# EA08AI-V2.net
KiCad netlist of a schematic drawn in Altium Designer
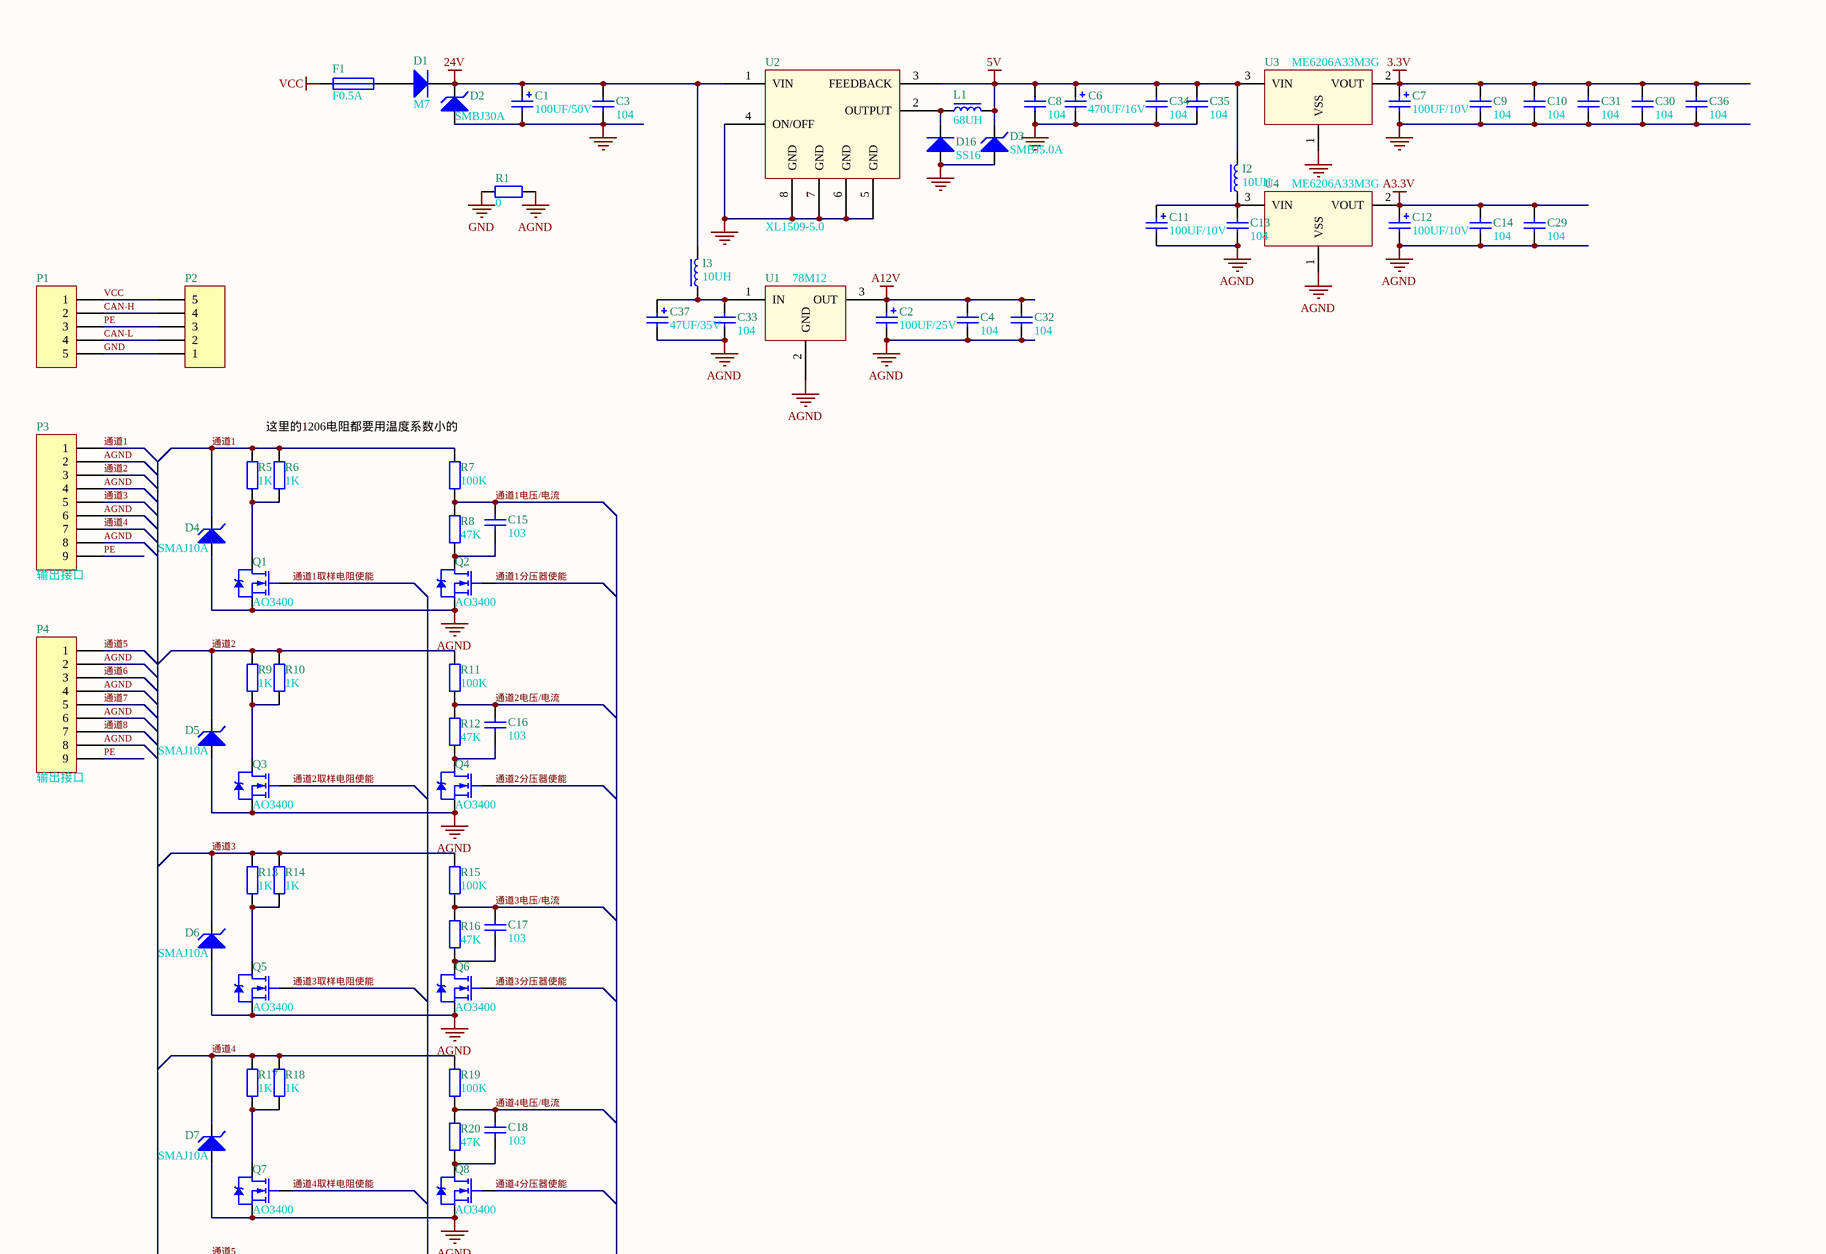
[diagram p0: EA08AI-V2.SchDoc, top]
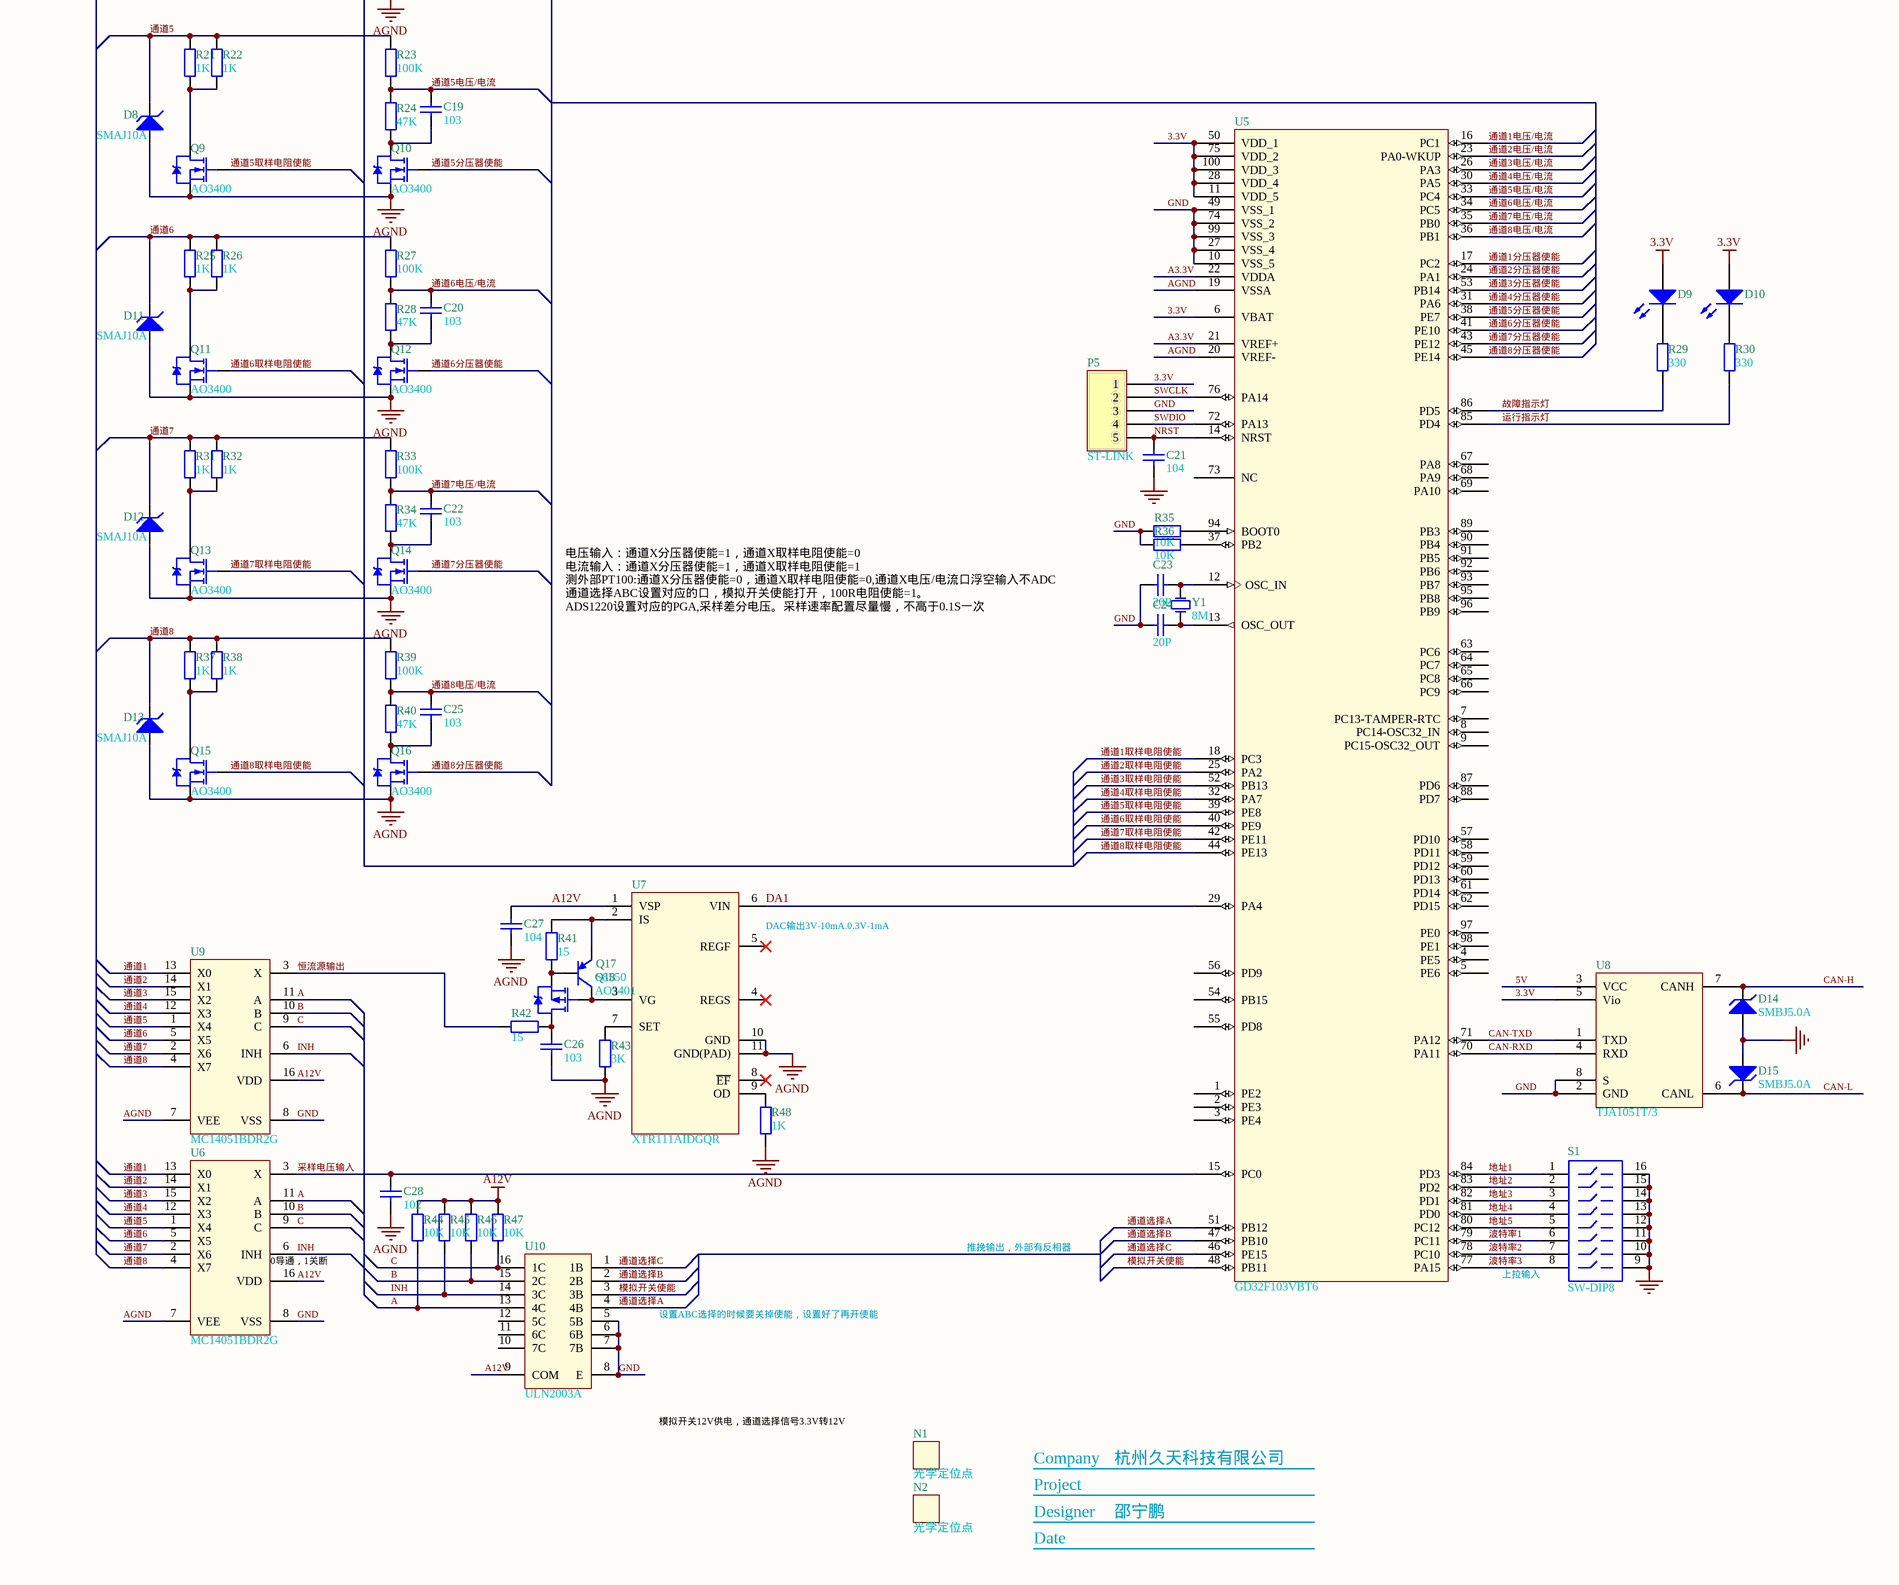
[diagram p1: EA08AI-V2.SchDoc, bottom]

(export (version "E")
  (design (tool "Eeschema 10.0.6"))
  (components
    (comp (ref "C1")
      (value "100UF/50V")
      (footprint "贴片固态电容8*10-M")
      (description "Polarized Capacitor (Radial)")
      (fields (field (name "PUBLISHER") "Altium Limited"))
      (libsource (lib "元件2.0") (part "Cap Pol1"))
    )
    (comp (ref "C2")
      (value "100UF/25V")
      (footprint "贴片固态电容6.3*5.3-M")
      (description "Polarized Capacitor (Radial)")
      (fields (field (name "PUBLISHER") "Altium Limited"))
      (libsource (lib "元件2.0") (part "Cap Pol1"))
    )
    (comp (ref "C3")
      (value "104")
      (footprint "C-0603")
      (description "Capacitor")
      (fields (field (name "PUBLISHER") "Altium Limited"))
      (libsource (lib "元件2.0") (part "Cap"))
    )
    (comp (ref "C4")
      (value "104")
      (footprint "C-0603")
      (description "Capacitor")
      (fields (field (name "PUBLISHER") "Altium Limited"))
      (libsource (lib "元件2.0") (part "Cap"))
    )
    (comp (ref "C6")
      (value "470UF/16V")
      (footprint "贴片固态电容8*10-M")
      (description "Polarized Capacitor (Radial)")
      (fields (field (name "PUBLISHER") "Altium Limited"))
      (libsource (lib "元件2.0") (part "Cap Pol1"))
    )
    (comp (ref "C7")
      (value "100UF/10V")
      (footprint "贴片固态电容5*5.3")
      (description "Polarized Capacitor (Radial)")
      (fields (field (name "PUBLISHER") "Altium Limited"))
      (libsource (lib "元件2.0") (part "Cap Pol1"))
    )
    (comp (ref "C8")
      (value "104")
      (footprint "C-0603")
      (description "Capacitor")
      (fields (field (name "PUBLISHER") "Altium Limited"))
      (libsource (lib "元件2.0") (part "Cap"))
    )
    (comp (ref "C9")
      (value "104")
      (footprint "C-0603")
      (description "Capacitor")
      (fields (field (name "PUBLISHER") "Altium Limited"))
      (libsource (lib "元件2.0") (part "Cap"))
    )
    (comp (ref "C10")
      (value "104")
      (footprint "C-0603")
      (description "Capacitor")
      (fields (field (name "PUBLISHER") "Altium Limited"))
      (libsource (lib "元件2.0") (part "Cap"))
    )
    (comp (ref "C11")
      (value "100UF/10V")
      (footprint "贴片固态电容5*5.3")
      (description "Polarized Capacitor (Radial)")
      (fields (field (name "PUBLISHER") "Altium Limited"))
      (libsource (lib "元件2.0") (part "Cap Pol1"))
    )
    (comp (ref "C12")
      (value "100UF/10V")
      (footprint "贴片固态电容5*5.3")
      (description "Polarized Capacitor (Radial)")
      (fields (field (name "PUBLISHER") "Altium Limited"))
      (libsource (lib "元件2.0") (part "Cap Pol1"))
    )
    (comp (ref "C13")
      (value "104")
      (footprint "C-0603")
      (description "Capacitor")
      (fields (field (name "PUBLISHER") "Altium Limited"))
      (libsource (lib "元件2.0") (part "Cap"))
    )
    (comp (ref "C14")
      (value "104")
      (footprint "C-0603")
      (description "Capacitor")
      (fields (field (name "PUBLISHER") "Altium Limited"))
      (libsource (lib "元件2.0") (part "Cap"))
    )
    (comp (ref "C15")
      (value "103")
      (footprint "C-0603")
      (description "0805")
      (fields (field (name "PUBLISHER") "Altium Limited"))
      (libsource (lib "2电容-V1.0") (part "Cap-0603"))
    )
    (comp (ref "C16")
      (value "103")
      (footprint "C-0603")
      (description "0805")
      (fields (field (name "PUBLISHER") "Altium Limited"))
      (libsource (lib "2电容-V1.0") (part "Cap-0603"))
    )
    (comp (ref "C17")
      (value "103")
      (footprint "C-0603")
      (description "0805")
      (fields (field (name "PUBLISHER") "Altium Limited"))
      (libsource (lib "2电容-V1.0") (part "Cap-0603"))
    )
    (comp (ref "C18")
      (value "103")
      (footprint "C-0603")
      (description "0805")
      (fields (field (name "PUBLISHER") "Altium Limited"))
      (libsource (lib "2电容-V1.0") (part "Cap-0603"))
    )
    (comp (ref "C19")
      (value "103")
      (footprint "C-0603")
      (description "0805")
      (fields (field (name "PUBLISHER") "Altium Limited"))
      (libsource (lib "2电容-V1.0") (part "Cap-0603"))
    )
    (comp (ref "C20")
      (value "103")
      (footprint "C-0603")
      (description "0805")
      (fields (field (name "PUBLISHER") "Altium Limited"))
      (libsource (lib "2电容-V1.0") (part "Cap-0603"))
    )
    (comp (ref "C21")
      (value "104")
      (footprint "C-0603")
      (description "Capacitor")
      (fields (field (name "PUBLISHER") "Altium Limited"))
      (libsource (lib "元件2.0") (part "Cap"))
    )
    (comp (ref "C22")
      (value "103")
      (footprint "C-0603")
      (description "0805")
      (fields (field (name "PUBLISHER") "Altium Limited"))
      (libsource (lib "2电容-V1.0") (part "Cap-0603"))
    )
    (comp (ref "C23")
      (value "20P")
      (footprint "C-0603")
      (description "0805")
      (fields (field (name "PUBLISHER") "Altium Limited"))
      (libsource (lib "2电容-V1.0") (part "Cap-0603"))
    )
    (comp (ref "C24")
      (value "20P")
      (footprint "C-0603")
      (description "0805")
      (fields (field (name "PUBLISHER") "Altium Limited"))
      (libsource (lib "2电容-V1.0") (part "Cap-0603"))
    )
    (comp (ref "C25")
      (value "103")
      (footprint "C-0603")
      (description "0805")
      (fields (field (name "PUBLISHER") "Altium Limited"))
      (libsource (lib "2电容-V1.0") (part "Cap-0603"))
    )
    (comp (ref "C26")
      (value "103")
      (footprint "C-0603")
      (description "0805")
      (fields (field (name "PUBLISHER") "Altium Limited"))
      (libsource (lib "2电容-V1.0") (part "Cap-0603"))
    )
    (comp (ref "C27")
      (value "104")
      (footprint "C-0603")
      (description "Capacitor")
      (fields (field (name "PUBLISHER") "Altium Limited"))
      (libsource (lib "元件2.0") (part "Cap"))
    )
    (comp (ref "C28")
      (value "102")
      (footprint "C-0603")
      (description "Capacitor")
      (fields (field (name "PUBLISHER") "Altium Limited"))
      (libsource (lib "元件2.0") (part "Cap"))
    )
    (comp (ref "C29")
      (value "104")
      (footprint "C-0603")
      (description "Capacitor")
      (fields (field (name "PUBLISHER") "Altium Limited"))
      (libsource (lib "元件2.0") (part "Cap"))
    )
    (comp (ref "C30")
      (value "104")
      (footprint "C-0603")
      (description "Capacitor")
      (fields (field (name "PUBLISHER") "Altium Limited"))
      (libsource (lib "元件2.0") (part "Cap"))
    )
    (comp (ref "C31")
      (value "104")
      (footprint "C-0603")
      (description "Capacitor")
      (fields (field (name "PUBLISHER") "Altium Limited"))
      (libsource (lib "元件2.0") (part "Cap"))
    )
    (comp (ref "C32")
      (value "104")
      (footprint "C-0603")
      (description "Capacitor")
      (fields (field (name "PUBLISHER") "Altium Limited"))
      (libsource (lib "元件2.0") (part "Cap"))
    )
    (comp (ref "C33")
      (value "104")
      (footprint "C-0603")
      (description "Capacitor")
      (fields (field (name "PUBLISHER") "Altium Limited"))
      (libsource (lib "元件2.0") (part "Cap"))
    )
    (comp (ref "C34")
      (value "104")
      (footprint "C-0603")
      (description "Capacitor")
      (fields (field (name "PUBLISHER") "Altium Limited"))
      (libsource (lib "元件2.0") (part "Cap"))
    )
    (comp (ref "C35")
      (value "104")
      (footprint "C-0603")
      (description "Capacitor")
      (fields (field (name "PUBLISHER") "Altium Limited"))
      (libsource (lib "元件2.0") (part "Cap"))
    )
    (comp (ref "C36")
      (value "104")
      (footprint "C-0603")
      (description "Capacitor")
      (fields (field (name "PUBLISHER") "Altium Limited"))
      (libsource (lib "元件2.0") (part "Cap"))
    )
    (comp (ref "C37")
      (value "47UF/35V")
      (footprint "贴片固态电容6.3*5.3-M")
      (description "Polarized Capacitor (Radial)")
      (fields (field (name "PUBLISHER") "Altium Limited"))
      (libsource (lib "元件2.0") (part "Cap Pol1"))
    )
    (comp (ref "D1")
      (value "M7")
      (footprint "SMA")
      (description "SMA")
      (fields (field (name "PUBLISHER") "Altium Limited"))
      (libsource (lib "4二极管-V1.1") (part "M7"))
    )
    (comp (ref "D2")
      (value "SMBJ30A")
      (footprint "SMB")
      (description "SMB")
      (libsource (lib "4二极管-V1.1") (part "TVS-1"))
    )
    (comp (ref "D3")
      (value "SMBJ5.0A")
      (footprint "SMB")
      (description "SMB")
      (libsource (lib "4二极管-V1.1") (part "TVS-1"))
    )
    (comp (ref "D4")
      (value "SMAJ10A")
      (footprint "SMA")
      (description "SMB")
      (libsource (lib "4二极管-V1.1") (part "TVS-1"))
    )
    (comp (ref "D5")
      (value "SMAJ10A")
      (footprint "SMA")
      (description "SMB")
      (libsource (lib "4二极管-V1.1") (part "TVS-1"))
    )
    (comp (ref "D6")
      (value "SMAJ10A")
      (footprint "SMA")
      (description "SMB")
      (libsource (lib "4二极管-V1.1") (part "TVS-1"))
    )
    (comp (ref "D7")
      (value "SMAJ10A")
      (footprint "SMA")
      (description "SMB")
      (libsource (lib "4二极管-V1.1") (part "TVS-1"))
    )
    (comp (ref "D8")
      (value "SMAJ10A")
      (footprint "SMA")
      (description "SMB")
      (libsource (lib "4二极管-V1.1") (part "TVS-1"))
    )
    (comp (ref "D9")
      (value "~")
      (footprint "LED Φ3红2.54mm")
      (fields (field (name "PUBLISHER") "Altium Limited"))
      (libsource (lib "4二极管-V1.1") (part "LED-0603-Blue"))
    )
    (comp (ref "D10")
      (value "~")
      (footprint "LED Φ3绿2.54mm")
      (fields (field (name "PUBLISHER") "Altium Limited"))
      (libsource (lib "4二极管-V1.1") (part "LED-0603-Blue"))
    )
    (comp (ref "D11")
      (value "SMAJ10A")
      (footprint "SMA")
      (description "SMB")
      (libsource (lib "4二极管-V1.1") (part "TVS-1"))
    )
    (comp (ref "D12")
      (value "SMAJ10A")
      (footprint "SMA")
      (description "SMB")
      (libsource (lib "4二极管-V1.1") (part "TVS-1"))
    )
    (comp (ref "D13")
      (value "SMAJ10A")
      (footprint "SMA")
      (description "SMB")
      (libsource (lib "4二极管-V1.1") (part "TVS-1"))
    )
    (comp (ref "D14")
      (value "SMBJ5.0A")
      (footprint "SMB")
      (description "SMB")
      (libsource (lib "4二极管-V1.1") (part "TVS-1"))
    )
    (comp (ref "D15")
      (value "SMBJ5.0A")
      (footprint "SMB")
      (description "SMB")
      (libsource (lib "4二极管-V1.1") (part "TVS-1"))
    )
    (comp (ref "D16")
      (value "SS16")
      (footprint "SMA")
      (description "SMA")
      (libsource (lib "4二极管-V1.1") (part "SS14"))
    )
    (comp (ref "F1")
      (value "F0.5A")
      (footprint "FUSE-1808")
      (description "Fuse")
      (fields (field (name "PUBLISHER") "Altium Limited"))
      (libsource (lib "11其他元件-V1.0") (part "Fuse 1"))
    )
    (comp (ref "I2") (value "10UH") (footprint "CD54") (libsource (lib "3电感-V1.0") (part "Inductance3")))
    (comp (ref "I3") (value "10UH") (footprint "CD54") (libsource (lib "3电感-V1.0") (part "Inductance3")))
    (comp (ref "L1") (value "68UH") (footprint "CD75") (libsource (lib "3电感-V1.0") (part "Inductance3")))
    (comp (ref "N1") (value "光学定位点") (footprint "MARK-1mm-3mm") (libsource (lib "11其他元件-V1.0") (part "无引脚")))
    (comp (ref "N2") (value "光学定位点") (footprint "MARK-1mm-3mm") (libsource (lib "11其他元件-V1.0") (part "无引脚")))
    (comp (ref "P1")
      (value "~")
      (footprint "弯针5.08-M-5P")
      (description "Header, 5-Pin")
      (fields (field (name "PUBLISHER") "Altium Limited"))
      (libsource (lib "5排针-V1.0") (part "Header 5"))
    )
    (comp (ref "P2")
      (value "~")
      (footprint "KF2EDGVC-5.08-5P弯针")
      (description "Header, 5-Pin")
      (fields (field (name "PUBLISHER") "Altium Limited"))
      (libsource (lib "") (part "Header 5_1"))
    )
    (comp (ref "P3")
      (value "输出接口")
      (footprint "KF2EDGVC-5.08-9P")
      (description "Header, 9-Pin")
      (fields (field (name "PUBLISHER") "Altium Limited"))
      (libsource (lib "5排针-V1.0") (part "Header 9"))
    )
    (comp (ref "P4")
      (value "输出接口")
      (footprint "KF2EDGVC-5.08-9P")
      (description "Header, 9-Pin")
      (fields (field (name "PUBLISHER") "Altium Limited"))
      (libsource (lib "5排针-V1.0") (part "Header 9"))
    )
    (comp (ref "P5")
      (value "ST-LINK")
      (footprint "5P下载口")
      (description "Header, 5-Pin")
      (fields (field (name "PUBLISHER") "Altium Limited"))
      (libsource (lib "5排针-V1.0") (part "Header 5"))
    )
    (comp (ref "Q1")
      (value "AO3400")
      (footprint "SOT-23")
      (description "SOT-23")
      (libsource (lib "4二极管-V1.1") (part "AO3400"))
    )
    (comp (ref "Q2")
      (value "AO3400")
      (footprint "SOT-23")
      (description "SOT-23")
      (libsource (lib "4二极管-V1.1") (part "AO3400"))
    )
    (comp (ref "Q3")
      (value "AO3400")
      (footprint "SOT-23")
      (description "SOT-23")
      (libsource (lib "4二极管-V1.1") (part "AO3400"))
    )
    (comp (ref "Q4")
      (value "AO3400")
      (footprint "SOT-23")
      (description "SOT-23")
      (libsource (lib "4二极管-V1.1") (part "AO3400"))
    )
    (comp (ref "Q5")
      (value "AO3400")
      (footprint "SOT-23")
      (description "SOT-23")
      (libsource (lib "4二极管-V1.1") (part "AO3400"))
    )
    (comp (ref "Q6")
      (value "AO3400")
      (footprint "SOT-23")
      (description "SOT-23")
      (libsource (lib "4二极管-V1.1") (part "AO3400"))
    )
    (comp (ref "Q7")
      (value "AO3400")
      (footprint "SOT-23")
      (description "SOT-23")
      (libsource (lib "4二极管-V1.1") (part "AO3400"))
    )
    (comp (ref "Q8")
      (value "AO3400")
      (footprint "SOT-23")
      (description "SOT-23")
      (libsource (lib "4二极管-V1.1") (part "AO3400"))
    )
    (comp (ref "Q9")
      (value "AO3400")
      (footprint "SOT-23")
      (description "SOT-23")
      (libsource (lib "4二极管-V1.1") (part "AO3400"))
    )
    (comp (ref "Q10")
      (value "AO3400")
      (footprint "SOT-23")
      (description "SOT-23")
      (libsource (lib "4二极管-V1.1") (part "AO3400"))
    )
    (comp (ref "Q11")
      (value "AO3400")
      (footprint "SOT-23")
      (description "SOT-23")
      (libsource (lib "4二极管-V1.1") (part "AO3400"))
    )
    (comp (ref "Q12")
      (value "AO3400")
      (footprint "SOT-23")
      (description "SOT-23")
      (libsource (lib "4二极管-V1.1") (part "AO3400"))
    )
    (comp (ref "Q13")
      (value "AO3400")
      (footprint "SOT-23")
      (description "SOT-23")
      (libsource (lib "4二极管-V1.1") (part "AO3400"))
    )
    (comp (ref "Q14")
      (value "AO3400")
      (footprint "SOT-23")
      (description "SOT-23")
      (libsource (lib "4二极管-V1.1") (part "AO3400"))
    )
    (comp (ref "Q15")
      (value "AO3400")
      (footprint "SOT-23")
      (description "SOT-23")
      (libsource (lib "4二极管-V1.1") (part "AO3400"))
    )
    (comp (ref "Q16")
      (value "AO3400")
      (footprint "SOT-23")
      (description "SOT-23")
      (libsource (lib "4二极管-V1.1") (part "AO3400"))
    )
    (comp (ref "Q17")
      (value "S8550")
      (footprint "SOT-23")
      (description "PNP SOT-23")
      (fields (field (name "PUBLISHER") "Altium Limited"))
      (libsource (lib "4二极管-V1.1") (part "S8550"))
    )
    (comp (ref "Q18")
      (value "AO3401")
      (footprint "SOT-23")
      (description "SOT-23")
      (libsource (lib "4二极管-V1.1") (part "AO3401"))
    )
    (comp (ref "R1")
      (value "0")
      (footprint "R-1206")
      (description "0603")
      (fields (field (name "PUBLISHER") "Altium Limited"))
      (libsource (lib "") (part "Res2-0603_1"))
    )
    (comp (ref "R5")
      (value "1K")
      (footprint "R-1206")
      (description "0603")
      (fields (field (name "PUBLISHER") "Altium Limited"))
      (libsource (lib "") (part "Res2-0603_1"))
    )
    (comp (ref "R6")
      (value "1K")
      (footprint "R-1206")
      (description "0603")
      (fields (field (name "PUBLISHER") "Altium Limited"))
      (libsource (lib "") (part "Res2-0603_1"))
    )
    (comp (ref "R7")
      (value "100K")
      (footprint "R-1206")
      (description "0603")
      (fields (field (name "PUBLISHER") "Altium Limited"))
      (libsource (lib "") (part "Res2-0603_1"))
    )
    (comp (ref "R8")
      (value "47K")
      (footprint "R-1206")
      (description "0603")
      (fields (field (name "PUBLISHER") "Altium Limited"))
      (libsource (lib "") (part "Res2-0603_1"))
    )
    (comp (ref "R9")
      (value "1K")
      (footprint "R-1206")
      (description "0603")
      (fields (field (name "PUBLISHER") "Altium Limited"))
      (libsource (lib "") (part "Res2-0603_1"))
    )
    (comp (ref "R10")
      (value "1K")
      (footprint "R-1206")
      (description "0603")
      (fields (field (name "PUBLISHER") "Altium Limited"))
      (libsource (lib "") (part "Res2-0603_1"))
    )
    (comp (ref "R11")
      (value "100K")
      (footprint "R-1206")
      (description "0603")
      (fields (field (name "PUBLISHER") "Altium Limited"))
      (libsource (lib "") (part "Res2-0603_1"))
    )
    (comp (ref "R12")
      (value "47K")
      (footprint "R-1206")
      (description "0603")
      (fields (field (name "PUBLISHER") "Altium Limited"))
      (libsource (lib "") (part "Res2-0603_1"))
    )
    (comp (ref "R13")
      (value "1K")
      (footprint "R-1206")
      (description "0603")
      (fields (field (name "PUBLISHER") "Altium Limited"))
      (libsource (lib "") (part "Res2-0603_1"))
    )
    (comp (ref "R14")
      (value "1K")
      (footprint "R-1206")
      (description "0603")
      (fields (field (name "PUBLISHER") "Altium Limited"))
      (libsource (lib "") (part "Res2-0603_1"))
    )
    (comp (ref "R15")
      (value "100K")
      (footprint "R-1206")
      (description "0603")
      (fields (field (name "PUBLISHER") "Altium Limited"))
      (libsource (lib "") (part "Res2-0603_1"))
    )
    (comp (ref "R16")
      (value "47K")
      (footprint "R-1206")
      (description "0603")
      (fields (field (name "PUBLISHER") "Altium Limited"))
      (libsource (lib "") (part "Res2-0603_1"))
    )
    (comp (ref "R17")
      (value "1K")
      (footprint "R-1206")
      (description "0603")
      (fields (field (name "PUBLISHER") "Altium Limited"))
      (libsource (lib "") (part "Res2-0603_1"))
    )
    (comp (ref "R18")
      (value "1K")
      (footprint "R-1206")
      (description "0603")
      (fields (field (name "PUBLISHER") "Altium Limited"))
      (libsource (lib "") (part "Res2-0603_1"))
    )
    (comp (ref "R19")
      (value "100K")
      (footprint "R-1206")
      (description "0603")
      (fields (field (name "PUBLISHER") "Altium Limited"))
      (libsource (lib "") (part "Res2-0603_1"))
    )
    (comp (ref "R20")
      (value "47K")
      (footprint "R-1206")
      (description "0603")
      (fields (field (name "PUBLISHER") "Altium Limited"))
      (libsource (lib "") (part "Res2-0603_1"))
    )
    (comp (ref "R21")
      (value "1K")
      (footprint "R-1206")
      (description "0603")
      (fields (field (name "PUBLISHER") "Altium Limited"))
      (libsource (lib "") (part "Res2-0603_1"))
    )
    (comp (ref "R22")
      (value "1K")
      (footprint "R-1206")
      (description "0603")
      (fields (field (name "PUBLISHER") "Altium Limited"))
      (libsource (lib "") (part "Res2-0603_1"))
    )
    (comp (ref "R23")
      (value "100K")
      (footprint "R-1206")
      (description "0603")
      (fields (field (name "PUBLISHER") "Altium Limited"))
      (libsource (lib "") (part "Res2-0603_1"))
    )
    (comp (ref "R24")
      (value "47K")
      (footprint "R-1206")
      (description "0603")
      (fields (field (name "PUBLISHER") "Altium Limited"))
      (libsource (lib "") (part "Res2-0603_1"))
    )
    (comp (ref "R25")
      (value "1K")
      (footprint "R-1206")
      (description "0603")
      (fields (field (name "PUBLISHER") "Altium Limited"))
      (libsource (lib "") (part "Res2-0603_1"))
    )
    (comp (ref "R26")
      (value "1K")
      (footprint "R-1206")
      (description "0603")
      (fields (field (name "PUBLISHER") "Altium Limited"))
      (libsource (lib "") (part "Res2-0603_1"))
    )
    (comp (ref "R27")
      (value "100K")
      (footprint "R-1206")
      (description "0603")
      (fields (field (name "PUBLISHER") "Altium Limited"))
      (libsource (lib "") (part "Res2-0603_1"))
    )
    (comp (ref "R28")
      (value "47K")
      (footprint "R-1206")
      (description "0603")
      (fields (field (name "PUBLISHER") "Altium Limited"))
      (libsource (lib "") (part "Res2-0603_1"))
    )
    (comp (ref "R29")
      (value "330")
      (footprint "R-0603")
      (description "0603")
      (fields (field (name "PUBLISHER") "Altium Limited"))
      (libsource (lib "") (part "Res2-0603_2"))
    )
    (comp (ref "R30")
      (value "330")
      (footprint "R-0603")
      (description "0603")
      (fields (field (name "PUBLISHER") "Altium Limited"))
      (libsource (lib "") (part "Res2-0603_2"))
    )
    (comp (ref "R31")
      (value "1K")
      (footprint "R-1206")
      (description "0603")
      (fields (field (name "PUBLISHER") "Altium Limited"))
      (libsource (lib "") (part "Res2-0603_1"))
    )
    (comp (ref "R32")
      (value "1K")
      (footprint "R-1206")
      (description "0603")
      (fields (field (name "PUBLISHER") "Altium Limited"))
      (libsource (lib "") (part "Res2-0603_1"))
    )
    (comp (ref "R33")
      (value "100K")
      (footprint "R-1206")
      (description "0603")
      (fields (field (name "PUBLISHER") "Altium Limited"))
      (libsource (lib "") (part "Res2-0603_1"))
    )
    (comp (ref "R34")
      (value "47K")
      (footprint "R-1206")
      (description "0603")
      (fields (field (name "PUBLISHER") "Altium Limited"))
      (libsource (lib "") (part "Res2-0603_1"))
    )
    (comp (ref "R35")
      (value "10K")
      (footprint "R-0603")
      (description "0603")
      (fields (field (name "PUBLISHER") "Altium Limited"))
      (libsource (lib "1电阻-V1.0") (part "Res2-0603"))
    )
    (comp (ref "R36")
      (value "10K")
      (footprint "R-0603")
      (description "0603")
      (fields (field (name "PUBLISHER") "Altium Limited"))
      (libsource (lib "1电阻-V1.0") (part "Res2-0603"))
    )
    (comp (ref "R37")
      (value "1K")
      (footprint "R-1206")
      (description "0603")
      (fields (field (name "PUBLISHER") "Altium Limited"))
      (libsource (lib "") (part "Res2-0603_1"))
    )
    (comp (ref "R38")
      (value "1K")
      (footprint "R-1206")
      (description "0603")
      (fields (field (name "PUBLISHER") "Altium Limited"))
      (libsource (lib "") (part "Res2-0603_1"))
    )
    (comp (ref "R39")
      (value "100K")
      (footprint "R-1206")
      (description "0603")
      (fields (field (name "PUBLISHER") "Altium Limited"))
      (libsource (lib "") (part "Res2-0603_1"))
    )
    (comp (ref "R40")
      (value "47K")
      (footprint "R-1206")
      (description "0603")
      (fields (field (name "PUBLISHER") "Altium Limited"))
      (libsource (lib "") (part "Res2-0603_1"))
    )
    (comp (ref "R41")
      (value "15")
      (footprint "R-1206")
      (description "0603")
      (fields (field (name "PUBLISHER") "Altium Limited"))
      (libsource (lib "1电阻-V1.0") (part "Res2-0603"))
    )
    (comp (ref "R42")
      (value "15")
      (footprint "R-1206")
      (description "0603")
      (fields (field (name "PUBLISHER") "Altium Limited"))
      (libsource (lib "") (part "Res2-0603_1"))
    )
    (comp (ref "R43")
      (value "3K")
      (footprint "R-0603")
      (description "0603")
      (fields (field (name "PUBLISHER") "Altium Limited"))
      (libsource (lib "1电阻-V1.0") (part "Res2-0603"))
    )
    (comp (ref "R44")
      (value "10K")
      (footprint "R-0603")
      (description "0603")
      (fields (field (name "PUBLISHER") "Altium Limited"))
      (libsource (lib "") (part "Res2-0603_2"))
    )
    (comp (ref "R45")
      (value "10K")
      (footprint "R-0603")
      (description "0603")
      (fields (field (name "PUBLISHER") "Altium Limited"))
      (libsource (lib "") (part "Res2-0603_2"))
    )
    (comp (ref "R46")
      (value "10K")
      (footprint "R-0603")
      (description "0603")
      (fields (field (name "PUBLISHER") "Altium Limited"))
      (libsource (lib "") (part "Res2-0603_2"))
    )
    (comp (ref "R47")
      (value "10K")
      (footprint "R-0603")
      (description "0603")
      (fields (field (name "PUBLISHER") "Altium Limited"))
      (libsource (lib "") (part "Res2-0603_2"))
    )
    (comp (ref "R48")
      (value "1K")
      (footprint "R-0603")
      (description "0603")
      (fields (field (name "PUBLISHER") "Altium Limited"))
      (libsource (lib "1电阻-V1.0") (part "Res2-0603"))
    )
    (comp (ref "S1")
      (value "SW-DIP8")
      (footprint "SW-蓝色拨码开关8P-加高")
      (fields (field (name "PUBLISHER") "Altium Limited"))
      (libsource (lib "开关-V1") (part "SW-DIP8"))
    )
    (comp (ref "U1")
      (value "78M12")
      (footprint "TO-252")
      (description "TO-252")
      (libsource (lib "电源芯片-线性稳压-V1") (part "78M05"))
    )
    (comp (ref "U2")
      (value "XL1509-5.0")
      (footprint "SOP-8-m")
      (description "开关电源 SOP-8")
      (libsource (lib "8集成电路-V1.1") (part "XL1509-ADJ"))
    )
    (comp (ref "U3")
      (value "ME6206A33M3G")
      (footprint "SOT-23")
      (description "LDO稳压 SOT-23")
      (libsource (lib "电源芯片-线性稳压-V1") (part "ME6206A33M3G"))
    )
    (comp (ref "U4")
      (value "ME6206A33M3G")
      (footprint "SOT-23")
      (description "LDO稳压 SOT-23")
      (libsource (lib "电源芯片-线性稳压-V1") (part "ME6206A33M3G"))
    )
    (comp (ref "U5")
      (value "GD32F103VBT6")
      (footprint "LQFP100-N")
      (libsource (lib "9单片机-V1.0") (part "GD32F103V"))
    )
    (comp (ref "U6")
      (value "MC14051BDR2G")
      (footprint "SOP-16-M")
      (libsource (lib "模拟开关") (part "MC14051BDR2G"))
    )
    (comp (ref "U7")
      (value "XTR111AIDGQR")
      (footprint "MSOP-10(11)-M")
      (description "4-20ma输出")
      (libsource (lib "8集成电路-V1.1") (part "XTR111"))
    )
    (comp (ref "U8") (value "TJA1051T/3") (footprint "SOP-8-m") (libsource (lib "通讯-V1") (part "TJA1051T/3")))
    (comp (ref "U9")
      (value "MC14051BDR2G")
      (footprint "SOP-16-M")
      (libsource (lib "模拟开关") (part "MC14051BDR2G"))
    )
    (comp (ref "U10")
      (value "ULN2003A")
      (footprint "SOP-16-M")
      (libsource (lib "8集成电路-V1.1") (part "ULN2003A"))
    )
    (comp (ref "Y1") (value "8M") (footprint "HC-49SMD") (libsource (lib "11其他元件-V1.0") (part "晶振")))
  )
  (nets
    (net (code "1") (name "/A") (class "Default")
      (node (ref "R44") (pin "1") (pinfunction "1_1") (pintype "passive"))
      (node (ref "U10") (pin "13") (pinfunction "4C_13") (pintype "passive"))
      (node (ref "U6") (pin "11") (pinfunction "A_11") (pintype "passive"))
      (node (ref "U9") (pin "11") (pinfunction "A_11") (pintype "passive"))
    )
    (net (code "2") (name "/B") (class "Default")
      (node (ref "R46") (pin "1") (pinfunction "1_1") (pintype "passive"))
      (node (ref "U10") (pin "15") (pinfunction "2C_15") (pintype "passive"))
      (node (ref "U6") (pin "10") (pinfunction "B_10") (pintype "passive"))
      (node (ref "U9") (pin "10") (pinfunction "B_10") (pintype "passive"))
    )
    (net (code "3") (name "/C") (class "Default")
      (node (ref "R47") (pin "1") (pinfunction "1_1") (pintype "passive"))
      (node (ref "U10") (pin "16") (pinfunction "1C_16") (pintype "passive"))
      (node (ref "U6") (pin "9") (pinfunction "C_9") (pintype "passive"))
      (node (ref "U9") (pin "9") (pinfunction "C_9") (pintype "passive"))
    )
    (net (code "4") (name "/CAN-H") (class "Default")
      (node (ref "D14") (pin "2") (pinfunction "K_2") (pintype "passive"))
      (node (ref "P1") (pin "2") (pinfunction "2_2") (pintype "passive"))
      (node (ref "P2") (pin "4") (pinfunction "4_4") (pintype "passive"))
      (node (ref "U8") (pin "7") (pinfunction "CANH_7") (pintype "passive"))
    )
    (net (code "5") (name "/CAN-L") (class "Default")
      (node (ref "D15") (pin "2") (pinfunction "K_2") (pintype "passive"))
      (node (ref "P1") (pin "4") (pinfunction "4_4") (pintype "passive"))
      (node (ref "P2") (pin "2") (pinfunction "2_2") (pintype "passive"))
      (node (ref "U8") (pin "6") (pinfunction "CANL_6") (pintype "passive"))
    )
    (net (code "6") (name "/CAN-RXD") (class "Default")
      (node (ref "U5") (pin "70") (pinfunction "PA11_70") (pintype "bidirectional"))
      (node (ref "U8") (pin "4") (pinfunction "RXD_4") (pintype "passive"))
    )
    (net (code "7") (name "/CAN-TXD") (class "Default")
      (node (ref "U5") (pin "71") (pinfunction "PA12_71") (pintype "bidirectional"))
      (node (ref "U8") (pin "1") (pinfunction "TXD_1") (pintype "passive"))
    )
    (net (code "8") (name "/DA1") (class "Default")
      (node (ref "U5") (pin "29") (pinfunction "PA4_29") (pintype "bidirectional"))
      (node (ref "U7") (pin "6") (pinfunction "VIN_6") (pintype "passive"))
    )
    (net (code "9") (name "/INH") (class "Default")
      (node (ref "R45") (pin "1") (pinfunction "1_1") (pintype "passive"))
      (node (ref "U10") (pin "14") (pinfunction "3C_14") (pintype "passive"))
      (node (ref "U6") (pin "6") (pinfunction "INH_6") (pintype "passive"))
      (node (ref "U9") (pin "6") (pinfunction "INH_6") (pintype "passive"))
    )
    (net (code "10") (name "/NRST") (class "Default")
      (node (ref "C21") (pin "2") (pinfunction "2_2") (pintype "passive"))
      (node (ref "P5") (pin "5") (pinfunction "5_5") (pintype "passive"))
      (node (ref "U5") (pin "14") (pinfunction "NRST_14") (pintype "bidirectional"))
    )
    (net (code "11") (name "/PE") (class "Default")
      (node (ref "P1") (pin "3") (pinfunction "3_3") (pintype "passive"))
      (node (ref "P2") (pin "3") (pinfunction "3_3") (pintype "passive"))
      (node (ref "P3") (pin "9") (pinfunction "9_9") (pintype "passive"))
      (node (ref "P4") (pin "9") (pinfunction "9_9") (pintype "passive"))
    )
    (net (code "12") (name "/SWCLK") (class "Default")
      (node (ref "P5") (pin "2") (pinfunction "2_2") (pintype "passive"))
      (node (ref "U5") (pin "76") (pinfunction "PA14_76") (pintype "bidirectional"))
    )
    (net (code "13") (name "/SWDIO") (class "Default")
      (node (ref "P5") (pin "4") (pinfunction "4_4") (pintype "passive"))
      (node (ref "U5") (pin "72") (pinfunction "PA13_72") (pintype "bidirectional"))
    )
    (net (code "14") (name "/地址1") (class "Default")
      (node (ref "S1") (pin "1") (pinfunction "1_1") (pintype "passive"))
      (node (ref "U5") (pin "84") (pinfunction "PD3_84") (pintype "bidirectional"))
    )
    (net (code "15") (name "/地址2") (class "Default")
      (node (ref "S1") (pin "2") (pinfunction "2_2") (pintype "passive"))
      (node (ref "U5") (pin "83") (pinfunction "PD2_83") (pintype "bidirectional"))
    )
    (net (code "16") (name "/地址3") (class "Default")
      (node (ref "S1") (pin "3") (pinfunction "3_3") (pintype "passive"))
      (node (ref "U5") (pin "82") (pinfunction "PD1_82") (pintype "bidirectional"))
    )
    (net (code "17") (name "/地址4") (class "Default")
      (node (ref "S1") (pin "4") (pinfunction "4_4") (pintype "passive"))
      (node (ref "U5") (pin "81") (pinfunction "PD0_81") (pintype "bidirectional"))
    )
    (net (code "18") (name "/地址5") (class "Default")
      (node (ref "S1") (pin "5") (pinfunction "5_5") (pintype "passive"))
      (node (ref "U5") (pin "80") (pinfunction "PC12_80") (pintype "bidirectional"))
    )
    (net (code "19") (name "/恒流源输出") (class "Default")
      (node (ref "R42") (pin "1") (pinfunction "1_1") (pintype "passive"))
      (node (ref "U9") (pin "3") (pinfunction "X_3") (pintype "passive"))
    )
    (net (code "20") (name "/故障指示灯") (class "Default")
      (node (ref "R29") (pin "1") (pinfunction "1_1") (pintype "passive"))
      (node (ref "U5") (pin "86") (pinfunction "PD5_86") (pintype "bidirectional"))
    )
    (net (code "21") (name "/模拟开关使能") (class "Default")
      (node (ref "U10") (pin "3") (pinfunction "3B_3") (pintype "passive"))
      (node (ref "U5") (pin "48") (pinfunction "PB11_48") (pintype "bidirectional"))
    )
    (net (code "22") (name "/波特率1") (class "Default")
      (node (ref "S1") (pin "6") (pinfunction "6_6") (pintype "passive"))
      (node (ref "U5") (pin "79") (pinfunction "PC11_79") (pintype "bidirectional"))
    )
    (net (code "23") (name "/波特率2") (class "Default")
      (node (ref "S1") (pin "7") (pinfunction "7_7") (pintype "passive"))
      (node (ref "U5") (pin "78") (pinfunction "PC10_78") (pintype "bidirectional"))
    )
    (net (code "24") (name "/波特率3") (class "Default")
      (node (ref "S1") (pin "8") (pinfunction "8_8") (pintype "passive"))
      (node (ref "U5") (pin "77") (pinfunction "PA15_77") (pintype "bidirectional"))
    )
    (net (code "25") (name "/运行指示灯") (class "Default")
      (node (ref "R30") (pin "1") (pinfunction "1_1") (pintype "passive"))
      (node (ref "U5") (pin "85") (pinfunction "PD4_85") (pintype "bidirectional"))
    )
    (net (code "26") (name "/通道1") (class "Default")
      (node (ref "D4") (pin "2") (pinfunction "K_2") (pintype "passive"))
      (node (ref "P3") (pin "1") (pinfunction "1_1") (pintype "passive"))
      (node (ref "R5") (pin "2") (pinfunction "2_2") (pintype "passive"))
      (node (ref "R6") (pin "2") (pinfunction "2_2") (pintype "passive"))
      (node (ref "R7") (pin "2") (pinfunction "2_2") (pintype "passive"))
      (node (ref "U6") (pin "13") (pinfunction "X0_13") (pintype "passive"))
      (node (ref "U9") (pin "13") (pinfunction "X0_13") (pintype "passive"))
    )
    (net (code "27") (name "/通道1分压器使能") (class "Default")
      (node (ref "Q2") (pin "1") (pinfunction "G_1") (pintype "passive"))
      (node (ref "U5") (pin "17") (pinfunction "PC2_17") (pintype "bidirectional"))
    )
    (net (code "28") (name "/通道1取样电阻使能") (class "Default")
      (node (ref "Q1") (pin "1") (pinfunction "G_1") (pintype "passive"))
      (node (ref "U5") (pin "18") (pinfunction "PC3_18") (pintype "bidirectional"))
    )
    (net (code "29") (name "/通道1电压{slash}电流") (class "Default")
      (node (ref "C15") (pin "2") (pinfunction "2_2") (pintype "passive"))
      (node (ref "R7") (pin "1") (pinfunction "1_1") (pintype "passive"))
      (node (ref "R8") (pin "2") (pinfunction "2_2") (pintype "passive"))
      (node (ref "U5") (pin "16") (pinfunction "PC1_16") (pintype "bidirectional"))
    )
    (net (code "30") (name "/通道2") (class "Default")
      (node (ref "D5") (pin "2") (pinfunction "K_2") (pintype "passive"))
      (node (ref "P3") (pin "3") (pinfunction "3_3") (pintype "passive"))
      (node (ref "R10") (pin "2") (pinfunction "2_2") (pintype "passive"))
      (node (ref "R11") (pin "2") (pinfunction "2_2") (pintype "passive"))
      (node (ref "R9") (pin "2") (pinfunction "2_2") (pintype "passive"))
      (node (ref "U6") (pin "14") (pinfunction "X1_14") (pintype "passive"))
      (node (ref "U9") (pin "14") (pinfunction "X1_14") (pintype "passive"))
    )
    (net (code "31") (name "/通道2分压器使能") (class "Default")
      (node (ref "Q4") (pin "1") (pinfunction "G_1") (pintype "passive"))
      (node (ref "U5") (pin "24") (pinfunction "PA1_24") (pintype "bidirectional"))
    )
    (net (code "32") (name "/通道2取样电阻使能") (class "Default")
      (node (ref "Q3") (pin "1") (pinfunction "G_1") (pintype "passive"))
      (node (ref "U5") (pin "25") (pinfunction "PA2_25") (pintype "bidirectional"))
    )
    (net (code "33") (name "/通道2电压{slash}电流") (class "Default")
      (node (ref "C16") (pin "2") (pinfunction "2_2") (pintype "passive"))
      (node (ref "R11") (pin "1") (pinfunction "1_1") (pintype "passive"))
      (node (ref "R12") (pin "2") (pinfunction "2_2") (pintype "passive"))
      (node (ref "U5") (pin "23") (pinfunction "PA0-WKUP_23") (pintype "bidirectional"))
    )
    (net (code "34") (name "/通道3") (class "Default")
      (node (ref "D6") (pin "2") (pinfunction "K_2") (pintype "passive"))
      (node (ref "P3") (pin "5") (pinfunction "5_5") (pintype "passive"))
      (node (ref "R13") (pin "2") (pinfunction "2_2") (pintype "passive"))
      (node (ref "R14") (pin "2") (pinfunction "2_2") (pintype "passive"))
      (node (ref "R15") (pin "2") (pinfunction "2_2") (pintype "passive"))
      (node (ref "U6") (pin "15") (pinfunction "X2_15") (pintype "passive"))
      (node (ref "U9") (pin "15") (pinfunction "X2_15") (pintype "passive"))
    )
    (net (code "35") (name "/通道3分压器使能") (class "Default")
      (node (ref "Q6") (pin "1") (pinfunction "G_1") (pintype "passive"))
      (node (ref "U5") (pin "53") (pinfunction "PB14_53") (pintype "bidirectional"))
    )
    (net (code "36") (name "/通道3取样电阻使能") (class "Default")
      (node (ref "Q5") (pin "1") (pinfunction "G_1") (pintype "passive"))
      (node (ref "U5") (pin "52") (pinfunction "PB13_52") (pintype "bidirectional"))
    )
    (net (code "37") (name "/通道3电压{slash}电流") (class "Default")
      (node (ref "C17") (pin "2") (pinfunction "2_2") (pintype "passive"))
      (node (ref "R15") (pin "1") (pinfunction "1_1") (pintype "passive"))
      (node (ref "R16") (pin "2") (pinfunction "2_2") (pintype "passive"))
      (node (ref "U5") (pin "26") (pinfunction "PA3_26") (pintype "bidirectional"))
    )
    (net (code "38") (name "/通道4") (class "Default")
      (node (ref "D7") (pin "2") (pinfunction "K_2") (pintype "passive"))
      (node (ref "P3") (pin "7") (pinfunction "7_7") (pintype "passive"))
      (node (ref "R17") (pin "2") (pinfunction "2_2") (pintype "passive"))
      (node (ref "R18") (pin "2") (pinfunction "2_2") (pintype "passive"))
      (node (ref "R19") (pin "2") (pinfunction "2_2") (pintype "passive"))
      (node (ref "U6") (pin "12") (pinfunction "X3_12") (pintype "passive"))
      (node (ref "U9") (pin "12") (pinfunction "X3_12") (pintype "passive"))
    )
    (net (code "39") (name "/通道4分压器使能") (class "Default")
      (node (ref "Q8") (pin "1") (pinfunction "G_1") (pintype "passive"))
      (node (ref "U5") (pin "31") (pinfunction "PA6_31") (pintype "bidirectional"))
    )
    (net (code "40") (name "/通道4取样电阻使能") (class "Default")
      (node (ref "Q7") (pin "1") (pinfunction "G_1") (pintype "passive"))
      (node (ref "U5") (pin "32") (pinfunction "PA7_32") (pintype "bidirectional"))
    )
    (net (code "41") (name "/通道4电压{slash}电流") (class "Default")
      (node (ref "C18") (pin "2") (pinfunction "2_2") (pintype "passive"))
      (node (ref "R19") (pin "1") (pinfunction "1_1") (pintype "passive"))
      (node (ref "R20") (pin "2") (pinfunction "2_2") (pintype "passive"))
      (node (ref "U5") (pin "30") (pinfunction "PA5_30") (pintype "bidirectional"))
    )
    (net (code "42") (name "/通道5") (class "Default")
      (node (ref "D8") (pin "2") (pinfunction "K_2") (pintype "passive"))
      (node (ref "P4") (pin "1") (pinfunction "1_1") (pintype "passive"))
      (node (ref "R21") (pin "2") (pinfunction "2_2") (pintype "passive"))
      (node (ref "R22") (pin "2") (pinfunction "2_2") (pintype "passive"))
      (node (ref "R23") (pin "2") (pinfunction "2_2") (pintype "passive"))
      (node (ref "U6") (pin "1") (pinfunction "X4_1") (pintype "passive"))
      (node (ref "U9") (pin "1") (pinfunction "X4_1") (pintype "passive"))
    )
    (net (code "43") (name "/通道5分压器使能") (class "Default")
      (node (ref "Q10") (pin "1") (pinfunction "G_1") (pintype "passive"))
      (node (ref "U5") (pin "38") (pinfunction "PE7_38") (pintype "bidirectional"))
    )
    (net (code "44") (name "/通道5取样电阻使能") (class "Default")
      (node (ref "Q9") (pin "1") (pinfunction "G_1") (pintype "passive"))
      (node (ref "U5") (pin "39") (pinfunction "PE8_39") (pintype "bidirectional"))
    )
    (net (code "45") (name "/通道5电压{slash}电流") (class "Default")
      (node (ref "C19") (pin "2") (pinfunction "2_2") (pintype "passive"))
      (node (ref "R23") (pin "1") (pinfunction "1_1") (pintype "passive"))
      (node (ref "R24") (pin "2") (pinfunction "2_2") (pintype "passive"))
      (node (ref "U5") (pin "33") (pinfunction "PC4_33") (pintype "bidirectional"))
    )
    (net (code "46") (name "/通道6") (class "Default")
      (node (ref "D11") (pin "2") (pinfunction "K_2") (pintype "passive"))
      (node (ref "P4") (pin "3") (pinfunction "3_3") (pintype "passive"))
      (node (ref "R25") (pin "2") (pinfunction "2_2") (pintype "passive"))
      (node (ref "R26") (pin "2") (pinfunction "2_2") (pintype "passive"))
      (node (ref "R27") (pin "2") (pinfunction "2_2") (pintype "passive"))
      (node (ref "U6") (pin "5") (pinfunction "X5_5") (pintype "passive"))
      (node (ref "U9") (pin "5") (pinfunction "X5_5") (pintype "passive"))
    )
    (net (code "47") (name "/通道6分压器使能") (class "Default")
      (node (ref "Q12") (pin "1") (pinfunction "G_1") (pintype "passive"))
      (node (ref "U5") (pin "41") (pinfunction "PE10_41") (pintype "bidirectional"))
    )
    (net (code "48") (name "/通道6取样电阻使能") (class "Default")
      (node (ref "Q11") (pin "1") (pinfunction "G_1") (pintype "passive"))
      (node (ref "U5") (pin "40") (pinfunction "PE9_40") (pintype "bidirectional"))
    )
    (net (code "49") (name "/通道6电压{slash}电流") (class "Default")
      (node (ref "C20") (pin "2") (pinfunction "2_2") (pintype "passive"))
      (node (ref "R27") (pin "1") (pinfunction "1_1") (pintype "passive"))
      (node (ref "R28") (pin "2") (pinfunction "2_2") (pintype "passive"))
      (node (ref "U5") (pin "34") (pinfunction "PC5_34") (pintype "bidirectional"))
    )
    (net (code "50") (name "/通道7") (class "Default")
      (node (ref "D12") (pin "2") (pinfunction "K_2") (pintype "passive"))
      (node (ref "P4") (pin "5") (pinfunction "5_5") (pintype "passive"))
      (node (ref "R31") (pin "2") (pinfunction "2_2") (pintype "passive"))
      (node (ref "R32") (pin "2") (pinfunction "2_2") (pintype "passive"))
      (node (ref "R33") (pin "2") (pinfunction "2_2") (pintype "passive"))
      (node (ref "U6") (pin "2") (pinfunction "X6_2") (pintype "passive"))
      (node (ref "U9") (pin "2") (pinfunction "X6_2") (pintype "passive"))
    )
    (net (code "51") (name "/通道7分压器使能") (class "Default")
      (node (ref "Q14") (pin "1") (pinfunction "G_1") (pintype "passive"))
      (node (ref "U5") (pin "43") (pinfunction "PE12_43") (pintype "bidirectional"))
    )
    (net (code "52") (name "/通道7取样电阻使能") (class "Default")
      (node (ref "Q13") (pin "1") (pinfunction "G_1") (pintype "passive"))
      (node (ref "U5") (pin "42") (pinfunction "PE11_42") (pintype "bidirectional"))
    )
    (net (code "53") (name "/通道7电压{slash}电流") (class "Default")
      (node (ref "C22") (pin "2") (pinfunction "2_2") (pintype "passive"))
      (node (ref "R33") (pin "1") (pinfunction "1_1") (pintype "passive"))
      (node (ref "R34") (pin "2") (pinfunction "2_2") (pintype "passive"))
      (node (ref "U5") (pin "35") (pinfunction "PB0_35") (pintype "bidirectional"))
    )
    (net (code "54") (name "/通道8") (class "Default")
      (node (ref "D13") (pin "2") (pinfunction "K_2") (pintype "passive"))
      (node (ref "P4") (pin "7") (pinfunction "7_7") (pintype "passive"))
      (node (ref "R37") (pin "2") (pinfunction "2_2") (pintype "passive"))
      (node (ref "R38") (pin "2") (pinfunction "2_2") (pintype "passive"))
      (node (ref "R39") (pin "2") (pinfunction "2_2") (pintype "passive"))
      (node (ref "U6") (pin "4") (pinfunction "X7_4") (pintype "passive"))
      (node (ref "U9") (pin "4") (pinfunction "X7_4") (pintype "passive"))
    )
    (net (code "55") (name "/通道8分压器使能") (class "Default")
      (node (ref "Q16") (pin "1") (pinfunction "G_1") (pintype "passive"))
      (node (ref "U5") (pin "45") (pinfunction "PE14_45") (pintype "bidirectional"))
    )
    (net (code "56") (name "/通道8取样电阻使能") (class "Default")
      (node (ref "Q15") (pin "1") (pinfunction "G_1") (pintype "passive"))
      (node (ref "U5") (pin "44") (pinfunction "PE13_44") (pintype "bidirectional"))
    )
    (net (code "57") (name "/通道8电压{slash}电流") (class "Default")
      (node (ref "C25") (pin "2") (pinfunction "2_2") (pintype "passive"))
      (node (ref "R39") (pin "1") (pinfunction "1_1") (pintype "passive"))
      (node (ref "R40") (pin "2") (pinfunction "2_2") (pintype "passive"))
      (node (ref "U5") (pin "36") (pinfunction "PB1_36") (pintype "bidirectional"))
    )
    (net (code "58") (name "/通道选择A") (class "Default")
      (node (ref "U10") (pin "4") (pinfunction "4B_4") (pintype "passive"))
      (node (ref "U5") (pin "51") (pinfunction "PB12_51") (pintype "bidirectional"))
    )
    (net (code "59") (name "/通道选择B") (class "Default")
      (node (ref "U10") (pin "2") (pinfunction "2B_2") (pintype "passive"))
      (node (ref "U5") (pin "47") (pinfunction "PB10_47") (pintype "bidirectional"))
    )
    (net (code "60") (name "/通道选择C") (class "Default")
      (node (ref "U10") (pin "1") (pinfunction "1B_1") (pintype "passive"))
      (node (ref "U5") (pin "46") (pinfunction "PE15_46") (pintype "bidirectional"))
    )
    (net (code "61") (name "/采样电压输入") (class "Default")
      (node (ref "C28") (pin "2") (pinfunction "2_2") (pintype "passive"))
      (node (ref "U5") (pin "15") (pinfunction "PC0_15") (pintype "bidirectional"))
      (node (ref "U6") (pin "3") (pinfunction "X_3") (pintype "passive"))
    )
    (net (code "62") (name "3.3V") (class "Default")
      (node (ref "C10") (pin "2") (pinfunction "2_2") (pintype "passive"))
      (node (ref "C30") (pin "2") (pinfunction "2_2") (pintype "passive"))
      (node (ref "C31") (pin "2") (pinfunction "2_2") (pintype "passive"))
      (node (ref "C36") (pin "2") (pinfunction "2_2") (pintype "passive"))
      (node (ref "C7") (pin "1") (pinfunction "1_1") (pintype "passive"))
      (node (ref "C9") (pin "2") (pinfunction "2_2") (pintype "passive"))
      (node (ref "D10") (pin "1") (pinfunction "A_1") (pintype "passive"))
      (node (ref "D9") (pin "1") (pinfunction "A_1") (pintype "passive"))
      (node (ref "P5") (pin "1") (pinfunction "1_1") (pintype "passive"))
      (node (ref "U3") (pin "2") (pinfunction "VOUT_2") (pintype "passive"))
      (node (ref "U5") (pin "100") (pinfunction "VDD_3_100") (pintype "power_in"))
      (node (ref "U5") (pin "11") (pinfunction "VDD_5_11") (pintype "power_in"))
      (node (ref "U5") (pin "28") (pinfunction "VDD_4_28") (pintype "power_in"))
      (node (ref "U5") (pin "50") (pinfunction "VDD_1_50") (pintype "power_in"))
      (node (ref "U5") (pin "6") (pinfunction "VBAT_6") (pintype "power_in"))
      (node (ref "U5") (pin "75") (pinfunction "VDD_2_75") (pintype "power_in"))
      (node (ref "U8") (pin "5") (pinfunction "Vio_5") (pintype "passive"))
    )
    (net (code "63") (name "5V") (class "Default")
      (node (ref "C34") (pin "2") (pinfunction "2_2") (pintype "passive"))
      (node (ref "C35") (pin "2") (pinfunction "2_2") (pintype "passive"))
      (node (ref "C6") (pin "1") (pinfunction "1_1") (pintype "passive"))
      (node (ref "C8") (pin "2") (pinfunction "2_2") (pintype "passive"))
      (node (ref "D3") (pin "2") (pinfunction "K_2") (pintype "passive"))
      (node (ref "I2") (pin "2") (pinfunction "2_2") (pintype "passive"))
      (node (ref "L1") (pin "2") (pinfunction "2_2") (pintype "passive"))
      (node (ref "U2") (pin "3") (pinfunction "FEEDBACK_3") (pintype "passive"))
      (node (ref "U3") (pin "3") (pinfunction "VIN_3") (pintype "passive"))
      (node (ref "U8") (pin "3") (pinfunction "VCC_3") (pintype "passive"))
    )
    (net (code "64") (name "24V") (class "Default")
      (node (ref "C1") (pin "1") (pinfunction "1_1") (pintype "passive"))
      (node (ref "C3") (pin "2") (pinfunction "2_2") (pintype "passive"))
      (node (ref "D1") (pin "2") (pinfunction "K_2") (pintype "passive"))
      (node (ref "D2") (pin "2") (pinfunction "K_2") (pintype "passive"))
      (node (ref "I3") (pin "2") (pinfunction "2_2") (pintype "passive"))
      (node (ref "U2") (pin "1") (pinfunction "VIN_1") (pintype "passive"))
    )
    (net (code "65") (name "A3.3V") (class "Default")
      (node (ref "C12") (pin "1") (pinfunction "1_1") (pintype "passive"))
      (node (ref "C14") (pin "2") (pinfunction "2_2") (pintype "passive"))
      (node (ref "C29") (pin "2") (pinfunction "2_2") (pintype "passive"))
      (node (ref "U4") (pin "2") (pinfunction "VOUT_2") (pintype "passive"))
      (node (ref "U5") (pin "21") (pinfunction "VREF+_21") (pintype "power_in"))
      (node (ref "U5") (pin "22") (pinfunction "VDDA_22") (pintype "power_in"))
    )
    (net (code "66") (name "A12V") (class "Default")
      (node (ref "C2") (pin "1") (pinfunction "1_1") (pintype "passive"))
      (node (ref "C27") (pin "2") (pinfunction "2_2") (pintype "passive"))
      (node (ref "C32") (pin "2") (pinfunction "2_2") (pintype "passive"))
      (node (ref "C4") (pin "2") (pinfunction "2_2") (pintype "passive"))
      (node (ref "R44") (pin "2") (pinfunction "2_2") (pintype "passive"))
      (node (ref "R45") (pin "2") (pinfunction "2_2") (pintype "passive"))
      (node (ref "R46") (pin "2") (pinfunction "2_2") (pintype "passive"))
      (node (ref "R47") (pin "2") (pinfunction "2_2") (pintype "passive"))
      (node (ref "U1") (pin "3") (pinfunction "OUT_3") (pintype "passive"))
      (node (ref "U10") (pin "9") (pinfunction "COM_9") (pintype "passive"))
      (node (ref "U6") (pin "16") (pinfunction "VDD_16") (pintype "passive"))
      (node (ref "U7") (pin "1") (pinfunction "VSP_1") (pintype "passive"))
      (node (ref "U9") (pin "16") (pinfunction "VDD_16") (pintype "passive"))
    )
    (net (code "67") (name "AGND") (class "Default")
      (node (ref "C11") (pin "2") (pinfunction "2_2") (pintype "passive"))
      (node (ref "C12") (pin "2") (pinfunction "2_2") (pintype "passive"))
      (node (ref "C13") (pin "1") (pinfunction "1_1") (pintype "passive"))
      (node (ref "C14") (pin "1") (pinfunction "1_1") (pintype "passive"))
      (node (ref "C2") (pin "2") (pinfunction "2_2") (pintype "passive"))
      (node (ref "C26") (pin "2") (pinfunction "2_2") (pintype "passive"))
      (node (ref "C27") (pin "1") (pinfunction "1_1") (pintype "passive"))
      (node (ref "C28") (pin "1") (pinfunction "1_1") (pintype "passive"))
      (node (ref "C29") (pin "1") (pinfunction "1_1") (pintype "passive"))
      (node (ref "C32") (pin "1") (pinfunction "1_1") (pintype "passive"))
      (node (ref "C33") (pin "1") (pinfunction "1_1") (pintype "passive"))
      (node (ref "C37") (pin "2") (pinfunction "2_2") (pintype "passive"))
      (node (ref "C4") (pin "1") (pinfunction "1_1") (pintype "passive"))
      (node (ref "D11") (pin "1") (pinfunction "A_1") (pintype "passive"))
      (node (ref "D12") (pin "1") (pinfunction "A_1") (pintype "passive"))
      (node (ref "D13") (pin "1") (pinfunction "A_1") (pintype "passive"))
      (node (ref "D4") (pin "1") (pinfunction "A_1") (pintype "passive"))
      (node (ref "D5") (pin "1") (pinfunction "A_1") (pintype "passive"))
      (node (ref "D6") (pin "1") (pinfunction "A_1") (pintype "passive"))
      (node (ref "D7") (pin "1") (pinfunction "A_1") (pintype "passive"))
      (node (ref "D8") (pin "1") (pinfunction "A_1") (pintype "passive"))
      (node (ref "P3") (pin "2") (pinfunction "2_2") (pintype "passive"))
      (node (ref "P3") (pin "4") (pinfunction "4_4") (pintype "passive"))
      (node (ref "P3") (pin "6") (pinfunction "6_6") (pintype "passive"))
      (node (ref "P3") (pin "8") (pinfunction "8_8") (pintype "passive"))
      (node (ref "P4") (pin "2") (pinfunction "2_2") (pintype "passive"))
      (node (ref "P4") (pin "4") (pinfunction "4_4") (pintype "passive"))
      (node (ref "P4") (pin "6") (pinfunction "6_6") (pintype "passive"))
      (node (ref "P4") (pin "8") (pinfunction "8_8") (pintype "passive"))
      (node (ref "Q1") (pin "2") (pinfunction "S_2") (pintype "passive"))
      (node (ref "Q10") (pin "2") (pinfunction "S_2") (pintype "passive"))
      (node (ref "Q11") (pin "2") (pinfunction "S_2") (pintype "passive"))
      (node (ref "Q12") (pin "2") (pinfunction "S_2") (pintype "passive"))
      (node (ref "Q13") (pin "2") (pinfunction "S_2") (pintype "passive"))
      (node (ref "Q14") (pin "2") (pinfunction "S_2") (pintype "passive"))
      (node (ref "Q15") (pin "2") (pinfunction "S_2") (pintype "passive"))
      (node (ref "Q16") (pin "2") (pinfunction "S_2") (pintype "passive"))
      (node (ref "Q2") (pin "2") (pinfunction "S_2") (pintype "passive"))
      (node (ref "Q3") (pin "2") (pinfunction "S_2") (pintype "passive"))
      (node (ref "Q4") (pin "2") (pinfunction "S_2") (pintype "passive"))
      (node (ref "Q5") (pin "2") (pinfunction "S_2") (pintype "passive"))
      (node (ref "Q6") (pin "2") (pinfunction "S_2") (pintype "passive"))
      (node (ref "Q7") (pin "2") (pinfunction "S_2") (pintype "passive"))
      (node (ref "Q8") (pin "2") (pinfunction "S_2") (pintype "passive"))
      (node (ref "Q9") (pin "2") (pinfunction "S_2") (pintype "passive"))
      (node (ref "R1") (pin "2") (pinfunction "2_2") (pintype "passive"))
      (node (ref "R43") (pin "2") (pinfunction "2_2") (pintype "passive"))
      (node (ref "R48") (pin "2") (pinfunction "2_2") (pintype "passive"))
      (node (ref "U1") (pin "2") (pinfunction "GND_2") (pintype "passive"))
      (node (ref "U4") (pin "1") (pinfunction "VSS_1") (pintype "passive"))
      (node (ref "U5") (pin "19") (pinfunction "VSSA_19") (pintype "power_in"))
      (node (ref "U5") (pin "20") (pinfunction "VREF-_20") (pintype "power_in"))
      (node (ref "U6") (pin "7") (pinfunction "VEE_7") (pintype "passive"))
      (node (ref "U7") (pin "10") (pinfunction "GND_10") (pintype "passive"))
      (node (ref "U7") (pin "11") (pinfunction "GND(PAD)_11") (pintype "passive"))
      (node (ref "U9") (pin "7") (pinfunction "VEE_7") (pintype "passive"))
    )
    (net (code "68") (name "GND") (class "Default")
      (node (ref "C1") (pin "2") (pinfunction "2_2") (pintype "passive"))
      (node (ref "C10") (pin "1") (pinfunction "1_1") (pintype "passive"))
      (node (ref "C21") (pin "1") (pinfunction "1_1") (pintype "passive"))
      (node (ref "C23") (pin "1") (pinfunction "1_1") (pintype "passive"))
      (node (ref "C24") (pin "1") (pinfunction "1_1") (pintype "passive"))
      (node (ref "C3") (pin "1") (pinfunction "1_1") (pintype "passive"))
      (node (ref "C30") (pin "1") (pinfunction "1_1") (pintype "passive"))
      (node (ref "C31") (pin "1") (pinfunction "1_1") (pintype "passive"))
      (node (ref "C34") (pin "1") (pinfunction "1_1") (pintype "passive"))
      (node (ref "C35") (pin "1") (pinfunction "1_1") (pintype "passive"))
      (node (ref "C36") (pin "1") (pinfunction "1_1") (pintype "passive"))
      (node (ref "C6") (pin "2") (pinfunction "2_2") (pintype "passive"))
      (node (ref "C7") (pin "2") (pinfunction "2_2") (pintype "passive"))
      (node (ref "C8") (pin "1") (pinfunction "1_1") (pintype "passive"))
      (node (ref "C9") (pin "1") (pinfunction "1_1") (pintype "passive"))
      (node (ref "D14") (pin "1") (pinfunction "A_1") (pintype "passive"))
      (node (ref "D15") (pin "1") (pinfunction "A_1") (pintype "passive"))
      (node (ref "D16") (pin "1") (pinfunction "A_1") (pintype "passive"))
      (node (ref "D2") (pin "1") (pinfunction "A_1") (pintype "passive"))
      (node (ref "D3") (pin "1") (pinfunction "A_1") (pintype "passive"))
      (node (ref "P1") (pin "5") (pinfunction "5_5") (pintype "passive"))
      (node (ref "P2") (pin "1") (pinfunction "1_1") (pintype "passive"))
      (node (ref "P5") (pin "3") (pinfunction "3_3") (pintype "passive"))
      (node (ref "R1") (pin "1") (pinfunction "1_1") (pintype "passive"))
      (node (ref "R35") (pin "2") (pinfunction "2_2") (pintype "passive"))
      (node (ref "R36") (pin "2") (pinfunction "2_2") (pintype "passive"))
      (node (ref "S1") (pin "10") (pinfunction "10_10") (pintype "passive"))
      (node (ref "S1") (pin "11") (pinfunction "11_11") (pintype "passive"))
      (node (ref "S1") (pin "12") (pinfunction "12_12") (pintype "passive"))
      (node (ref "S1") (pin "13") (pinfunction "13_13") (pintype "passive"))
      (node (ref "S1") (pin "14") (pinfunction "14_14") (pintype "passive"))
      (node (ref "S1") (pin "15") (pinfunction "15_15") (pintype "passive"))
      (node (ref "S1") (pin "16") (pinfunction "16_16") (pintype "passive"))
      (node (ref "S1") (pin "9") (pinfunction "9_9") (pintype "passive"))
      (node (ref "U10") (pin "5") (pinfunction "5B_5") (pintype "passive"))
      (node (ref "U10") (pin "6") (pinfunction "6B_6") (pintype "passive"))
      (node (ref "U10") (pin "7") (pinfunction "7B_7") (pintype "passive"))
      (node (ref "U10") (pin "8") (pinfunction "E_8") (pintype "passive"))
      (node (ref "U2") (pin "4") (pinfunction "ON/OFF_4") (pintype "passive"))
      (node (ref "U2") (pin "5") (pinfunction "GND_5") (pintype "passive"))
      (node (ref "U2") (pin "6") (pinfunction "GND_6") (pintype "passive"))
      (node (ref "U2") (pin "7") (pinfunction "GND_7") (pintype "passive"))
      (node (ref "U2") (pin "8") (pinfunction "GND_8") (pintype "passive"))
      (node (ref "U3") (pin "1") (pinfunction "VSS_1") (pintype "passive"))
      (node (ref "U5") (pin "10") (pinfunction "VSS_5_10") (pintype "power_in"))
      (node (ref "U5") (pin "27") (pinfunction "VSS_4_27") (pintype "power_in"))
      (node (ref "U5") (pin "49") (pinfunction "VSS_1_49") (pintype "power_in"))
      (node (ref "U5") (pin "74") (pinfunction "VSS_2_74") (pintype "power_in"))
      (node (ref "U5") (pin "99") (pinfunction "VSS_3_99") (pintype "power_in"))
      (node (ref "U6") (pin "8") (pinfunction "VSS_8") (pintype "passive"))
      (node (ref "U8") (pin "2") (pinfunction "GND_2") (pintype "passive"))
      (node (ref "U8") (pin "8") (pinfunction "S_8") (pintype "passive"))
      (node (ref "U9") (pin "8") (pinfunction "VSS_8") (pintype "passive"))
    )
    (net (code "69") (name "Net-(D1-A)") (class "Default")
      (node (ref "D1") (pin "1") (pinfunction "A_1") (pintype "passive"))
      (node (ref "F1") (pin "2") (pinfunction "2_2") (pintype "passive"))
    )
    (net (code "70") (name "Net-(D9-K)") (class "Default")
      (node (ref "D9") (pin "2") (pinfunction "K_2") (pintype "passive"))
      (node (ref "R29") (pin "2") (pinfunction "2_2") (pintype "passive"))
    )
    (net (code "71") (name "Net-(D10-K)") (class "Default")
      (node (ref "D10") (pin "2") (pinfunction "K_2") (pintype "passive"))
      (node (ref "R30") (pin "2") (pinfunction "2_2") (pintype "passive"))
    )
    (net (code "72") (name "Net-(D16-K)") (class "Default")
      (node (ref "D16") (pin "2") (pinfunction "K_2") (pintype "passive"))
      (node (ref "L1") (pin "1") (pinfunction "1_1") (pintype "passive"))
      (node (ref "U2") (pin "2") (pinfunction "OUTPUT_2") (pintype "passive"))
    )
    (net (code "73") (name "Net-(Q1-D)") (class "Default")
      (node (ref "Q1") (pin "3") (pinfunction "D_3") (pintype "passive"))
      (node (ref "R5") (pin "1") (pinfunction "1_1") (pintype "passive"))
      (node (ref "R6") (pin "1") (pinfunction "1_1") (pintype "passive"))
    )
    (net (code "74") (name "Net-(Q2-D)") (class "Default")
      (node (ref "C15") (pin "1") (pinfunction "1_1") (pintype "passive"))
      (node (ref "Q2") (pin "3") (pinfunction "D_3") (pintype "passive"))
      (node (ref "R8") (pin "1") (pinfunction "1_1") (pintype "passive"))
    )
    (net (code "75") (name "Net-(Q3-D)") (class "Default")
      (node (ref "Q3") (pin "3") (pinfunction "D_3") (pintype "passive"))
      (node (ref "R10") (pin "1") (pinfunction "1_1") (pintype "passive"))
      (node (ref "R9") (pin "1") (pinfunction "1_1") (pintype "passive"))
    )
    (net (code "76") (name "Net-(Q4-D)") (class "Default")
      (node (ref "C16") (pin "1") (pinfunction "1_1") (pintype "passive"))
      (node (ref "Q4") (pin "3") (pinfunction "D_3") (pintype "passive"))
      (node (ref "R12") (pin "1") (pinfunction "1_1") (pintype "passive"))
    )
    (net (code "77") (name "Net-(Q5-D)") (class "Default")
      (node (ref "Q5") (pin "3") (pinfunction "D_3") (pintype "passive"))
      (node (ref "R13") (pin "1") (pinfunction "1_1") (pintype "passive"))
      (node (ref "R14") (pin "1") (pinfunction "1_1") (pintype "passive"))
    )
    (net (code "78") (name "Net-(Q6-D)") (class "Default")
      (node (ref "C17") (pin "1") (pinfunction "1_1") (pintype "passive"))
      (node (ref "Q6") (pin "3") (pinfunction "D_3") (pintype "passive"))
      (node (ref "R16") (pin "1") (pinfunction "1_1") (pintype "passive"))
    )
    (net (code "79") (name "Net-(Q7-D)") (class "Default")
      (node (ref "Q7") (pin "3") (pinfunction "D_3") (pintype "passive"))
      (node (ref "R17") (pin "1") (pinfunction "1_1") (pintype "passive"))
      (node (ref "R18") (pin "1") (pinfunction "1_1") (pintype "passive"))
    )
    (net (code "80") (name "Net-(Q8-D)") (class "Default")
      (node (ref "C18") (pin "1") (pinfunction "1_1") (pintype "passive"))
      (node (ref "Q8") (pin "3") (pinfunction "D_3") (pintype "passive"))
      (node (ref "R20") (pin "1") (pinfunction "1_1") (pintype "passive"))
    )
    (net (code "81") (name "Net-(Q9-D)") (class "Default")
      (node (ref "Q9") (pin "3") (pinfunction "D_3") (pintype "passive"))
      (node (ref "R21") (pin "1") (pinfunction "1_1") (pintype "passive"))
      (node (ref "R22") (pin "1") (pinfunction "1_1") (pintype "passive"))
    )
    (net (code "82") (name "Net-(Q10-D)") (class "Default")
      (node (ref "C19") (pin "1") (pinfunction "1_1") (pintype "passive"))
      (node (ref "Q10") (pin "3") (pinfunction "D_3") (pintype "passive"))
      (node (ref "R24") (pin "1") (pinfunction "1_1") (pintype "passive"))
    )
    (net (code "83") (name "Net-(Q11-D)") (class "Default")
      (node (ref "Q11") (pin "3") (pinfunction "D_3") (pintype "passive"))
      (node (ref "R25") (pin "1") (pinfunction "1_1") (pintype "passive"))
      (node (ref "R26") (pin "1") (pinfunction "1_1") (pintype "passive"))
    )
    (net (code "84") (name "Net-(Q12-D)") (class "Default")
      (node (ref "C20") (pin "1") (pinfunction "1_1") (pintype "passive"))
      (node (ref "Q12") (pin "3") (pinfunction "D_3") (pintype "passive"))
      (node (ref "R28") (pin "1") (pinfunction "1_1") (pintype "passive"))
    )
    (net (code "85") (name "Net-(Q13-D)") (class "Default")
      (node (ref "Q13") (pin "3") (pinfunction "D_3") (pintype "passive"))
      (node (ref "R31") (pin "1") (pinfunction "1_1") (pintype "passive"))
      (node (ref "R32") (pin "1") (pinfunction "1_1") (pintype "passive"))
    )
    (net (code "86") (name "Net-(Q14-D)") (class "Default")
      (node (ref "C22") (pin "1") (pinfunction "1_1") (pintype "passive"))
      (node (ref "Q14") (pin "3") (pinfunction "D_3") (pintype "passive"))
      (node (ref "R34") (pin "1") (pinfunction "1_1") (pintype "passive"))
    )
    (net (code "87") (name "Net-(Q15-D)") (class "Default")
      (node (ref "Q15") (pin "3") (pinfunction "D_3") (pintype "passive"))
      (node (ref "R37") (pin "1") (pinfunction "1_1") (pintype "passive"))
      (node (ref "R38") (pin "1") (pinfunction "1_1") (pintype "passive"))
    )
    (net (code "88") (name "Net-(Q16-D)") (class "Default")
      (node (ref "C25") (pin "1") (pinfunction "1_1") (pintype "passive"))
      (node (ref "Q16") (pin "3") (pinfunction "D_3") (pintype "passive"))
      (node (ref "R40") (pin "1") (pinfunction "1_1") (pintype "passive"))
    )
    (net (code "89") (name "Net-(Q17-B)") (class "Default")
      (node (ref "Q17") (pin "1") (pinfunction "B_1") (pintype "passive"))
      (node (ref "Q18") (pin "2") (pinfunction "S_2") (pintype "passive"))
      (node (ref "R41") (pin "2") (pinfunction "2_2") (pintype "passive"))
    )
    (net (code "90") (name "Net-(Q17-C)") (class "Default")
      (node (ref "Q17") (pin "3") (pinfunction "C_3") (pintype "passive"))
      (node (ref "Q18") (pin "1") (pinfunction "G_1") (pintype "passive"))
      (node (ref "U7") (pin "3") (pinfunction "VG_3") (pintype "passive"))
    )
    (net (code "91") (name "Net-(Q17-E)") (class "Default")
      (node (ref "Q17") (pin "2") (pinfunction "E_2") (pintype "passive"))
      (node (ref "R41") (pin "1") (pinfunction "1_1") (pintype "passive"))
      (node (ref "U7") (pin "2") (pinfunction "IS_2") (pintype "passive"))
    )
    (net (code "92") (name "Net-(Q18-D)") (class "Default")
      (node (ref "C26") (pin "1") (pinfunction "1_1") (pintype "passive"))
      (node (ref "Q18") (pin "3") (pinfunction "D_3") (pintype "passive"))
      (node (ref "R42") (pin "2") (pinfunction "2_2") (pintype "passive"))
    )
    (net (code "93") (name "Net-(U1-IN)") (class "Default")
      (node (ref "C33") (pin "2") (pinfunction "2_2") (pintype "passive"))
      (node (ref "C37") (pin "1") (pinfunction "1_1") (pintype "passive"))
      (node (ref "I3") (pin "1") (pinfunction "1_1") (pintype "passive"))
      (node (ref "U1") (pin "1") (pinfunction "IN_1") (pintype "passive"))
    )
    (net (code "94") (name "Net-(U4-VIN)") (class "Default")
      (node (ref "C11") (pin "1") (pinfunction "1_1") (pintype "passive"))
      (node (ref "C13") (pin "2") (pinfunction "2_2") (pintype "passive"))
      (node (ref "I2") (pin "1") (pinfunction "1_1") (pintype "passive"))
      (node (ref "U4") (pin "3") (pinfunction "VIN_3") (pintype "passive"))
    )
    (net (code "95") (name "Net-(U5-BOOT0)") (class "Default")
      (node (ref "R35") (pin "1") (pinfunction "1_1") (pintype "passive"))
      (node (ref "U5") (pin "94") (pinfunction "BOOT0_94") (pintype "input"))
    )
    (net (code "96") (name "Net-(U5-OSC_IN)") (class "Default")
      (node (ref "C23") (pin "2") (pinfunction "2_2") (pintype "passive"))
      (node (ref "U5") (pin "12") (pinfunction "OSC_IN_12") (pintype "input"))
      (node (ref "Y1") (pin "2") (pinfunction "OSC2_2") (pintype "passive"))
    )
    (net (code "97") (name "Net-(U5-OSC_OUT)") (class "Default")
      (node (ref "C24") (pin "2") (pinfunction "2_2") (pintype "passive"))
      (node (ref "U5") (pin "13") (pinfunction "OSC_OUT_13") (pintype "output"))
      (node (ref "Y1") (pin "1") (pinfunction "OSC1_1") (pintype "passive"))
    )
    (net (code "98") (name "Net-(U5-PB2)") (class "Default")
      (node (ref "R36") (pin "1") (pinfunction "1_1") (pintype "passive"))
      (node (ref "U5") (pin "37") (pinfunction "PB2_37") (pintype "bidirectional"))
    )
    (net (code "99") (name "Net-(U7-OD)") (class "Default")
      (node (ref "R48") (pin "1") (pinfunction "1_1") (pintype "passive"))
      (node (ref "U7") (pin "9") (pinfunction "OD_9") (pintype "passive"))
    )
    (net (code "100") (name "Net-(U7-SET)") (class "Default")
      (node (ref "R43") (pin "1") (pinfunction "1_1") (pintype "passive"))
      (node (ref "U7") (pin "7") (pinfunction "SET_7") (pintype "passive"))
    )
    (net (code "101") (name "VCC") (class "Default")
      (node (ref "F1") (pin "1") (pinfunction "1_1") (pintype "passive"))
      (node (ref "P1") (pin "1") (pinfunction "1_1") (pintype "passive"))
      (node (ref "P2") (pin "5") (pinfunction "5_5") (pintype "passive"))
    )
    (net (code "102") (name "unconnected-(U5-NC-Pad73)") (class "Default")
      (node (ref "U5") (pin "73") (pinfunction "NC_73") (pintype "passive"))
    )
    (net (code "103") (name "unconnected-(U5-PA8-Pad67)") (class "Default")
      (node (ref "U5") (pin "67") (pinfunction "PA8_67") (pintype "bidirectional"))
    )
    (net (code "104") (name "unconnected-(U5-PA9-Pad68)") (class "Default")
      (node (ref "U5") (pin "68") (pinfunction "PA9_68") (pintype "bidirectional"))
    )
    (net (code "105") (name "unconnected-(U5-PA10-Pad69)") (class "Default")
      (node (ref "U5") (pin "69") (pinfunction "PA10_69") (pintype "bidirectional"))
    )
    (net (code "106") (name "unconnected-(U5-PB3-Pad89)") (class "Default")
      (node (ref "U5") (pin "89") (pinfunction "PB3_89") (pintype "bidirectional"))
    )
    (net (code "107") (name "unconnected-(U5-PB4-Pad90)") (class "Default")
      (node (ref "U5") (pin "90") (pinfunction "PB4_90") (pintype "bidirectional"))
    )
    (net (code "108") (name "unconnected-(U5-PB5-Pad91)") (class "Default")
      (node (ref "U5") (pin "91") (pinfunction "PB5_91") (pintype "bidirectional"))
    )
    (net (code "109") (name "unconnected-(U5-PB6-Pad92)") (class "Default")
      (node (ref "U5") (pin "92") (pinfunction "PB6_92") (pintype "bidirectional"))
    )
    (net (code "110") (name "unconnected-(U5-PB7-Pad93)") (class "Default")
      (node (ref "U5") (pin "93") (pinfunction "PB7_93") (pintype "bidirectional"))
    )
    (net (code "111") (name "unconnected-(U5-PB8-Pad95)") (class "Default")
      (node (ref "U5") (pin "95") (pinfunction "PB8_95") (pintype "bidirectional"))
    )
    (net (code "112") (name "unconnected-(U5-PB9-Pad96)") (class "Default")
      (node (ref "U5") (pin "96") (pinfunction "PB9_96") (pintype "bidirectional"))
    )
    (net (code "113") (name "unconnected-(U5-PB15-Pad54)") (class "Default")
      (node (ref "U5") (pin "54") (pinfunction "PB15_54") (pintype "bidirectional"))
    )
    (net (code "114") (name "unconnected-(U5-PC6-Pad63)") (class "Default")
      (node (ref "U5") (pin "63") (pinfunction "PC6_63") (pintype "bidirectional"))
    )
    (net (code "115") (name "unconnected-(U5-PC7-Pad64)") (class "Default")
      (node (ref "U5") (pin "64") (pinfunction "PC7_64") (pintype "bidirectional"))
    )
    (net (code "116") (name "unconnected-(U5-PC8-Pad65)") (class "Default")
      (node (ref "U5") (pin "65") (pinfunction "PC8_65") (pintype "bidirectional"))
    )
    (net (code "117") (name "unconnected-(U5-PC9-Pad66)") (class "Default")
      (node (ref "U5") (pin "66") (pinfunction "PC9_66") (pintype "bidirectional"))
    )
    (net (code "118") (name "unconnected-(U5-PC13-TAMPER-RTC-Pad7)") (class "Default")
      (node (ref "U5") (pin "7") (pinfunction "PC13-TAMPER-RTC_7") (pintype "bidirectional"))
    )
    (net (code "119") (name "unconnected-(U5-PC14-OSC32_IN-Pad8)") (class "Default")
      (node (ref "U5") (pin "8") (pinfunction "PC14-OSC32_IN_8") (pintype "bidirectional"))
    )
    (net (code "120") (name "unconnected-(U5-PC15-OSC32_OUT-Pad9)") (class "Default")
      (node (ref "U5") (pin "9") (pinfunction "PC15-OSC32_OUT_9") (pintype "bidirectional"))
    )
    (net (code "121") (name "unconnected-(U5-PD6-Pad87)") (class "Default")
      (node (ref "U5") (pin "87") (pinfunction "PD6_87") (pintype "bidirectional"))
    )
    (net (code "122") (name "unconnected-(U5-PD7-Pad88)") (class "Default")
      (node (ref "U5") (pin "88") (pinfunction "PD7_88") (pintype "bidirectional"))
    )
    (net (code "123") (name "unconnected-(U5-PD8-Pad55)") (class "Default")
      (node (ref "U5") (pin "55") (pinfunction "PD8_55") (pintype "bidirectional"))
    )
    (net (code "124") (name "unconnected-(U5-PD9-Pad56)") (class "Default")
      (node (ref "U5") (pin "56") (pinfunction "PD9_56") (pintype "bidirectional"))
    )
    (net (code "125") (name "unconnected-(U5-PD10-Pad57)") (class "Default")
      (node (ref "U5") (pin "57") (pinfunction "PD10_57") (pintype "bidirectional"))
    )
    (net (code "126") (name "unconnected-(U5-PD11-Pad58)") (class "Default")
      (node (ref "U5") (pin "58") (pinfunction "PD11_58") (pintype "bidirectional"))
    )
    (net (code "127") (name "unconnected-(U5-PD12-Pad59)") (class "Default")
      (node (ref "U5") (pin "59") (pinfunction "PD12_59") (pintype "bidirectional"))
    )
    (net (code "128") (name "unconnected-(U5-PD13-Pad60)") (class "Default")
      (node (ref "U5") (pin "60") (pinfunction "PD13_60") (pintype "bidirectional"))
    )
    (net (code "129") (name "unconnected-(U5-PD14-Pad61)") (class "Default")
      (node (ref "U5") (pin "61") (pinfunction "PD14_61") (pintype "bidirectional"))
    )
    (net (code "130") (name "unconnected-(U5-PD15-Pad62)") (class "Default")
      (node (ref "U5") (pin "62") (pinfunction "PD15_62") (pintype "bidirectional"))
    )
    (net (code "131") (name "unconnected-(U5-PE0-Pad97)") (class "Default")
      (node (ref "U5") (pin "97") (pinfunction "PE0_97") (pintype "bidirectional"))
    )
    (net (code "132") (name "unconnected-(U5-PE1-Pad98)") (class "Default")
      (node (ref "U5") (pin "98") (pinfunction "PE1_98") (pintype "bidirectional"))
    )
    (net (code "133") (name "unconnected-(U5-PE2-Pad1)") (class "Default")
      (node (ref "U5") (pin "1") (pinfunction "PE2_1") (pintype "bidirectional"))
    )
    (net (code "134") (name "unconnected-(U5-PE3-Pad2)") (class "Default")
      (node (ref "U5") (pin "2") (pinfunction "PE3_2") (pintype "bidirectional"))
    )
    (net (code "135") (name "unconnected-(U5-PE4-Pad3)") (class "Default")
      (node (ref "U5") (pin "3") (pinfunction "PE4_3") (pintype "bidirectional"))
    )
    (net (code "136") (name "unconnected-(U5-PE5-Pad4)") (class "Default")
      (node (ref "U5") (pin "4") (pinfunction "PE5_4") (pintype "bidirectional"))
    )
    (net (code "137") (name "unconnected-(U5-PE6-Pad5)") (class "Default")
      (node (ref "U5") (pin "5") (pinfunction "PE6_5") (pintype "bidirectional"))
    )
    (net (code "138") (name "unconnected-(U7-REGF-Pad5)") (class "Default")
      (node (ref "U7") (pin "5") (pinfunction "REGF_5") (pintype "passive+no_connect"))
    )
    (net (code "139") (name "unconnected-(U7-REGS-Pad4)") (class "Default")
      (node (ref "U7") (pin "4") (pinfunction "REGS_4") (pintype "passive+no_connect"))
    )
    (net (code "140") (name "unconnected-(U7-~{EF}-Pad8)") (class "Default")
      (node (ref "U7") (pin "8") (pinfunction "~{EF}_8") (pintype "passive+no_connect"))
    )
    (net (code "141") (name "unconnected-(U10-5C-Pad12)") (class "Default")
      (node (ref "U10") (pin "12") (pinfunction "5C_12") (pintype "passive"))
    )
    (net (code "142") (name "unconnected-(U10-6C-Pad11)") (class "Default")
      (node (ref "U10") (pin "11") (pinfunction "6C_11") (pintype "passive"))
    )
    (net (code "143") (name "unconnected-(U10-7C-Pad10)") (class "Default")
      (node (ref "U10") (pin "10") (pinfunction "7C_10") (pintype "passive"))
    )
  )
)
